# IGrevator.net
KiCad netlist of a schematic drawn in EAGLE
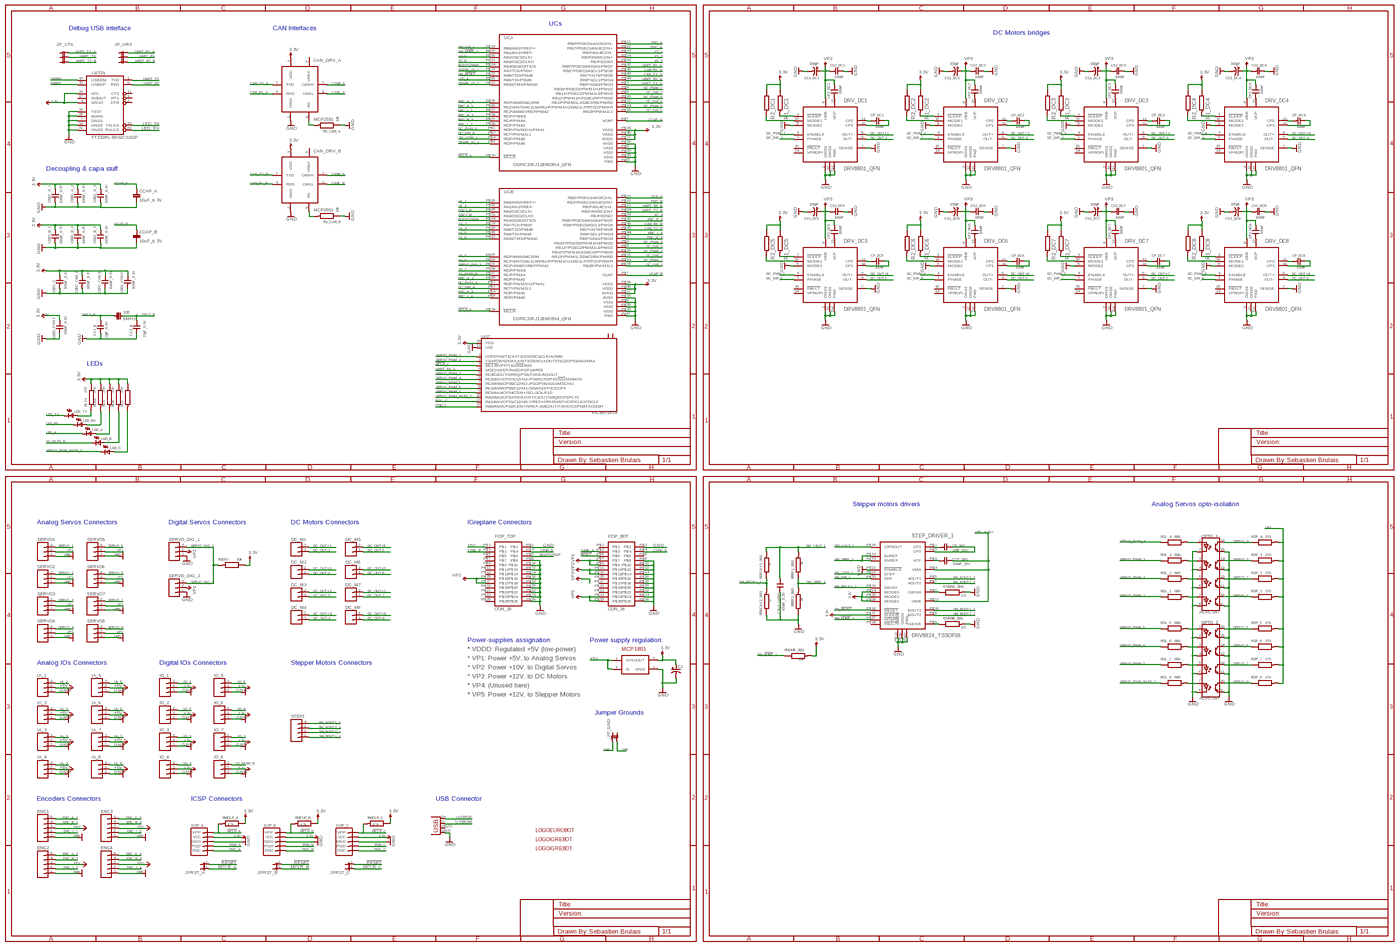
[diagram p0: schematic, sheet 1, overview]
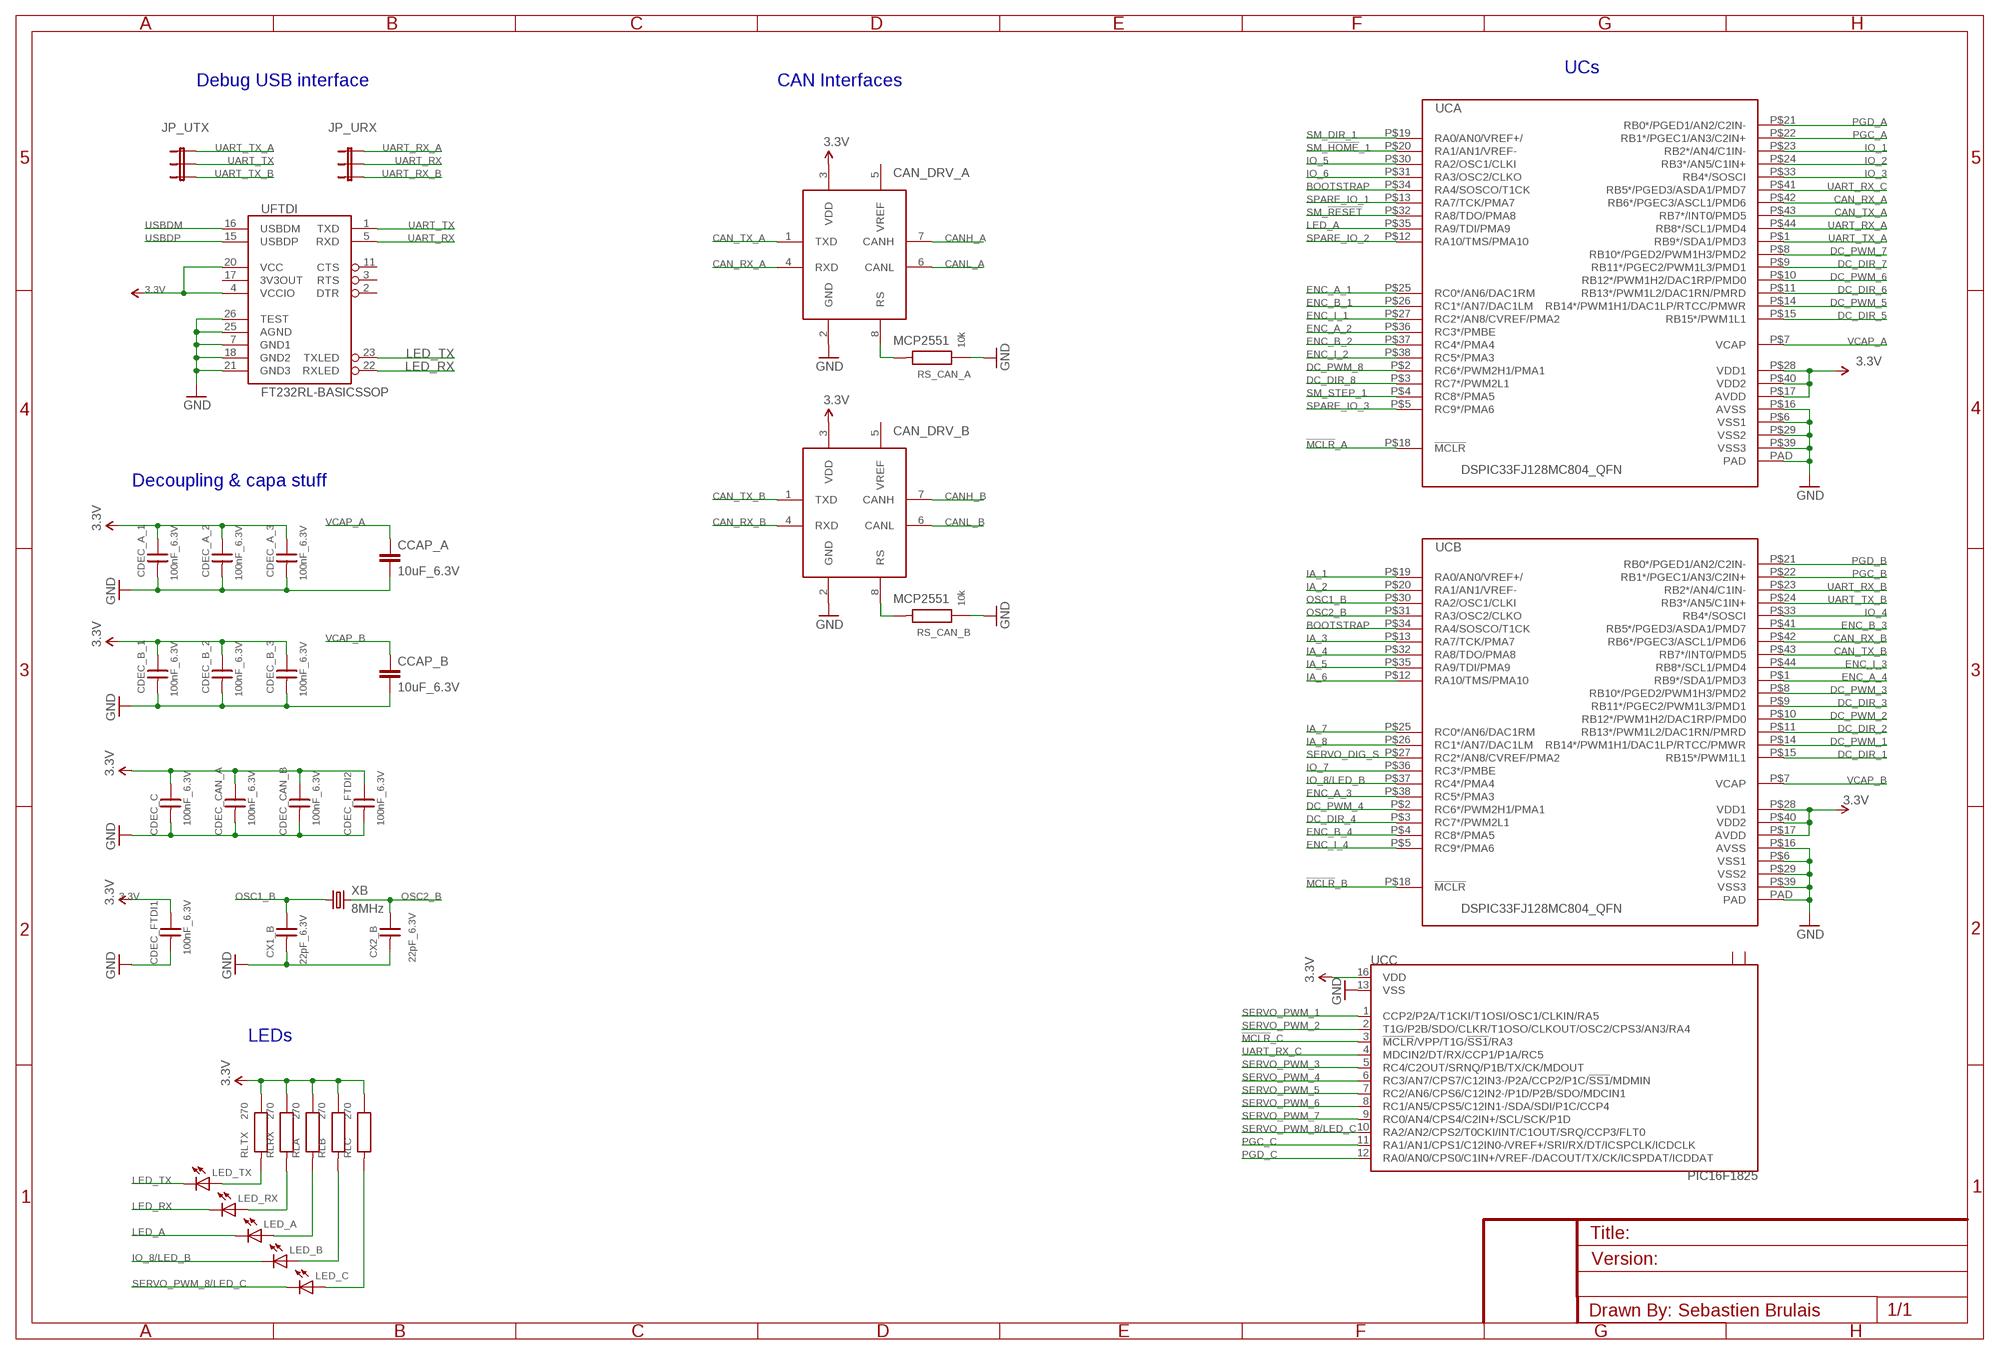
[diagram p1: schematic, sheet 1, part 1 of 4]
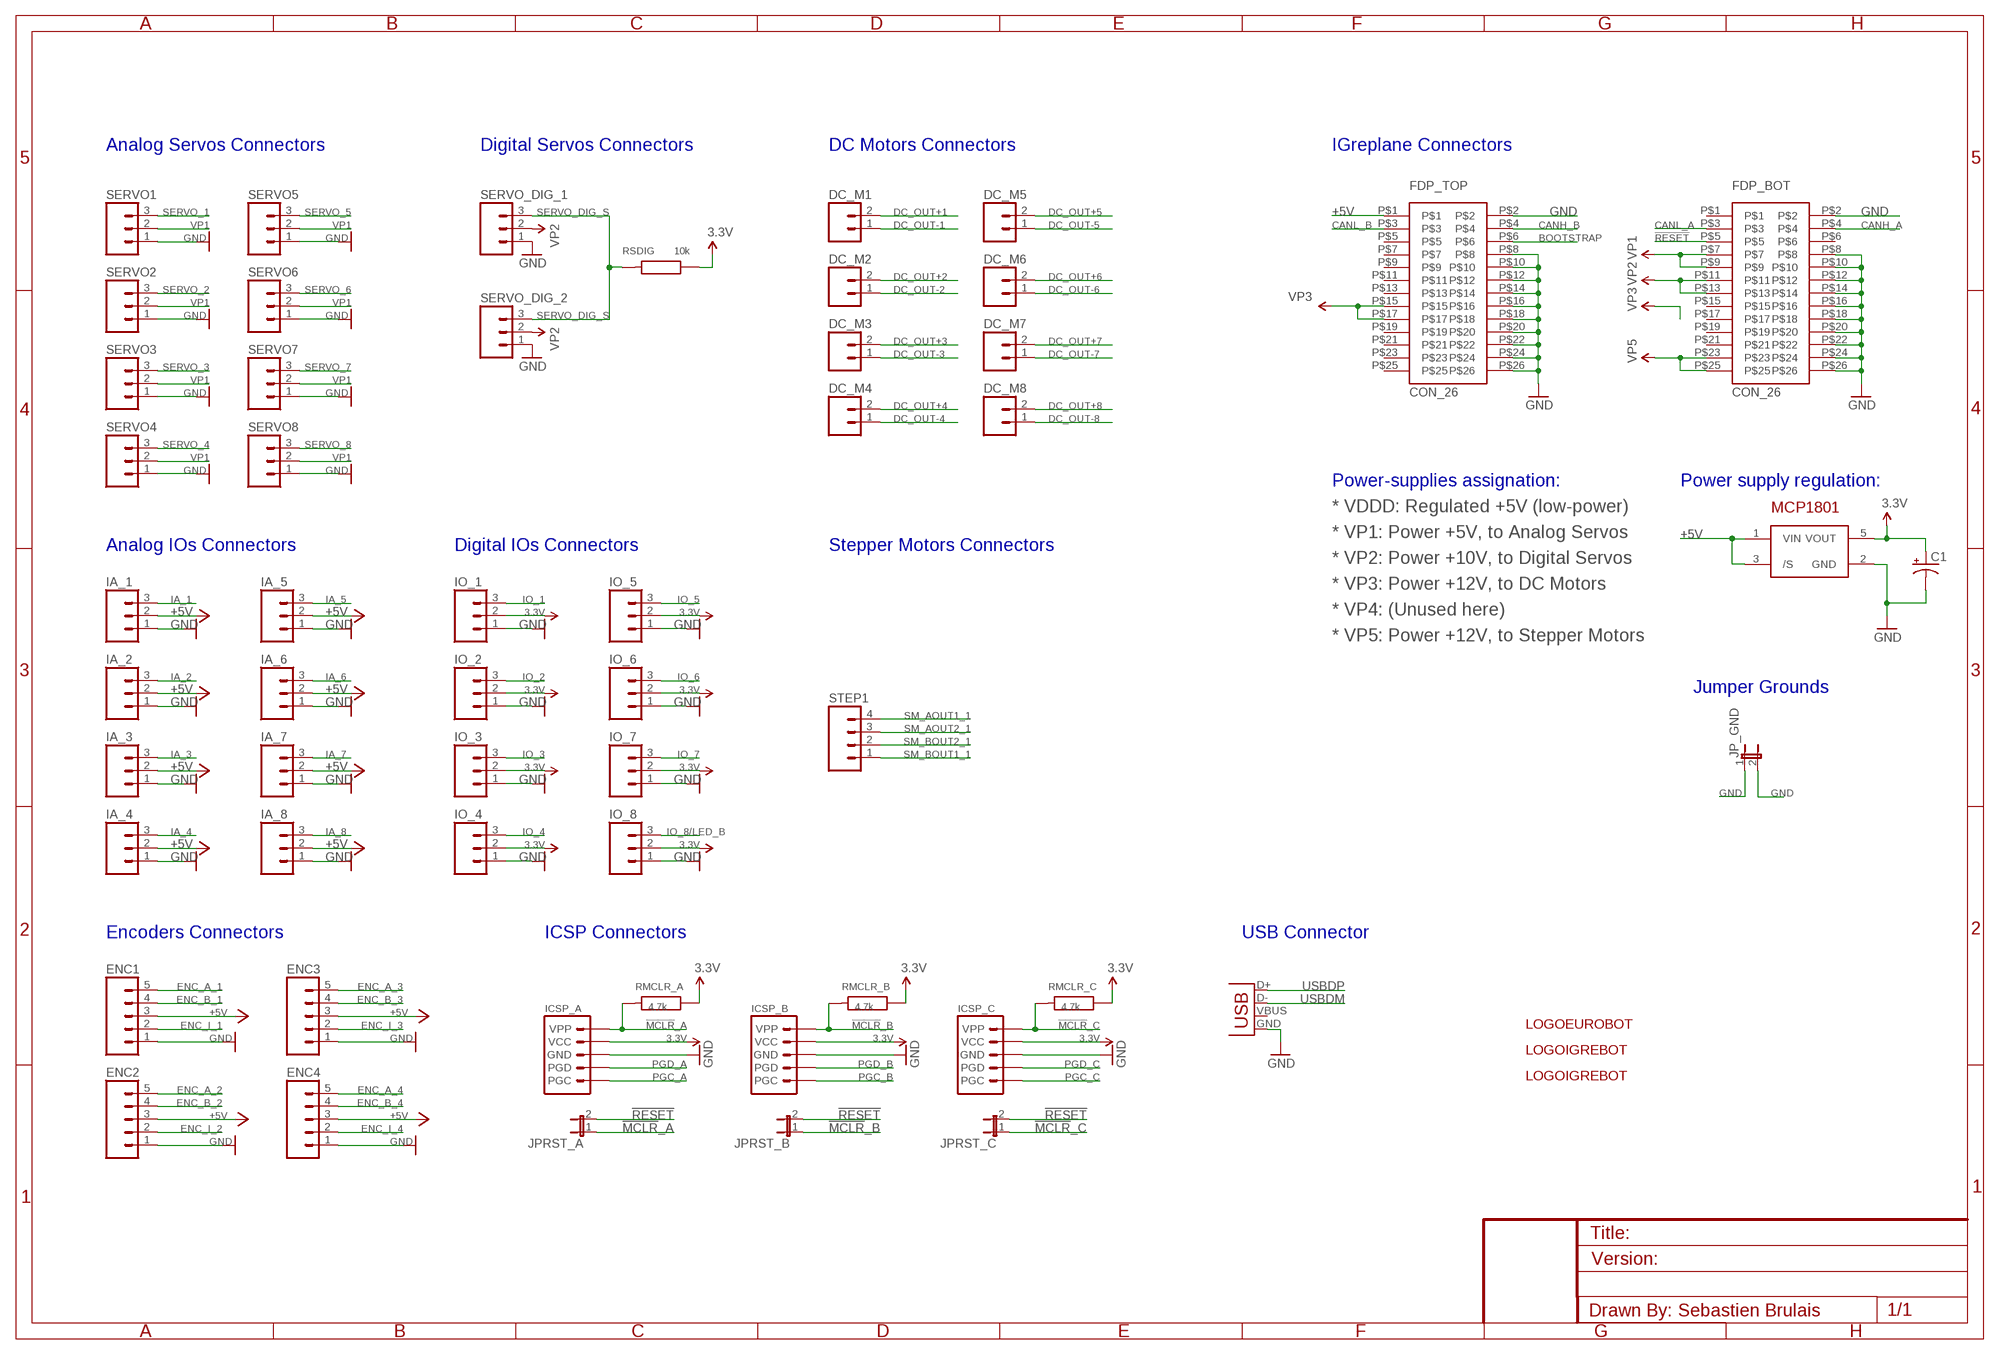
[diagram p2: schematic, sheet 1, part 2 of 4]
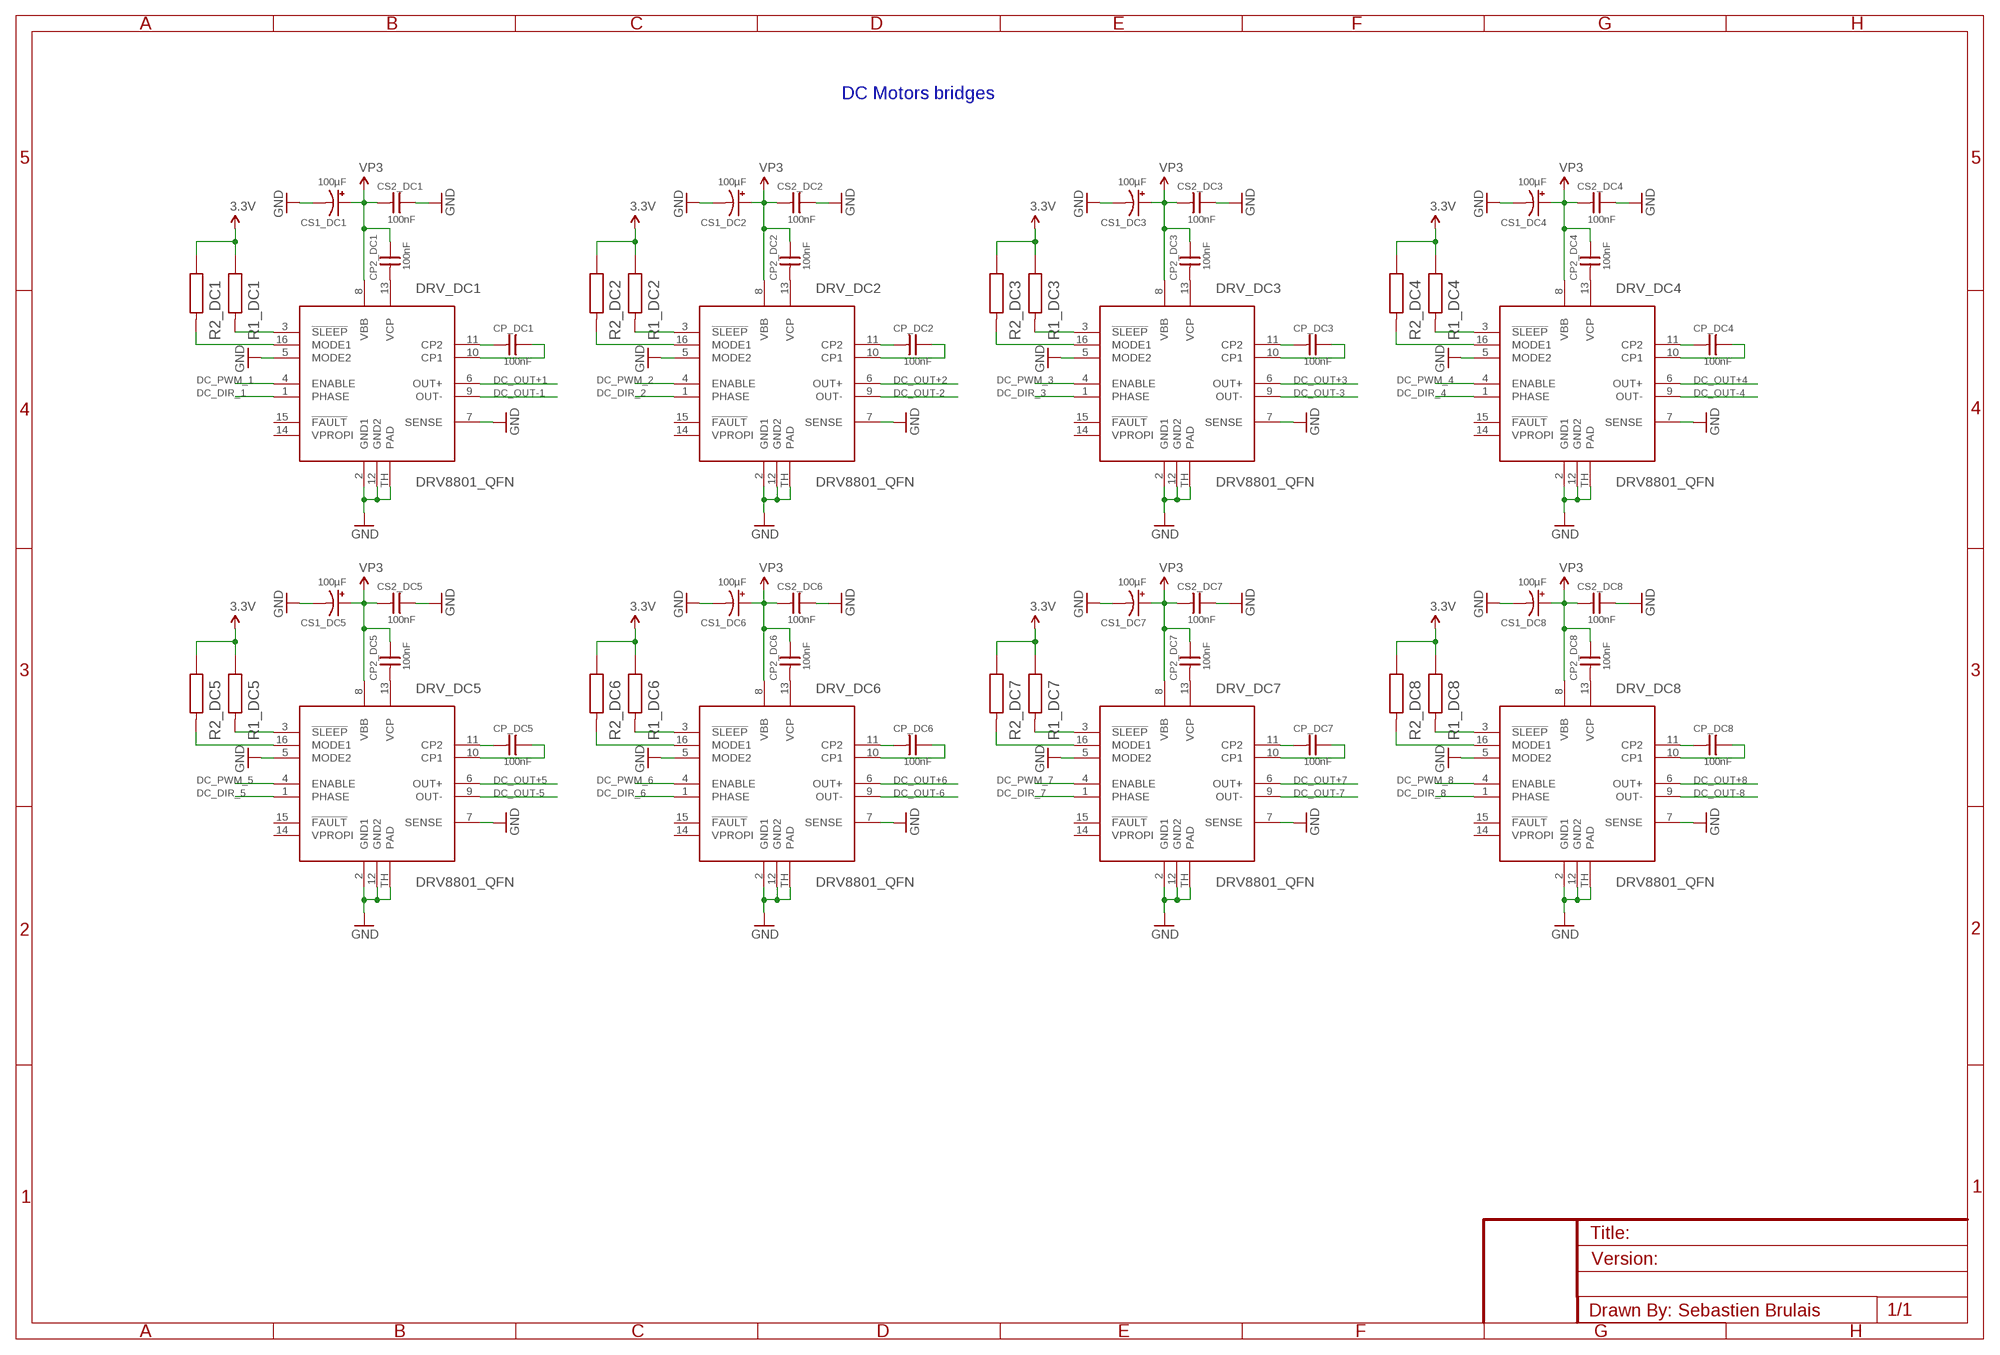
[diagram p3: schematic, sheet 1, part 3 of 4]
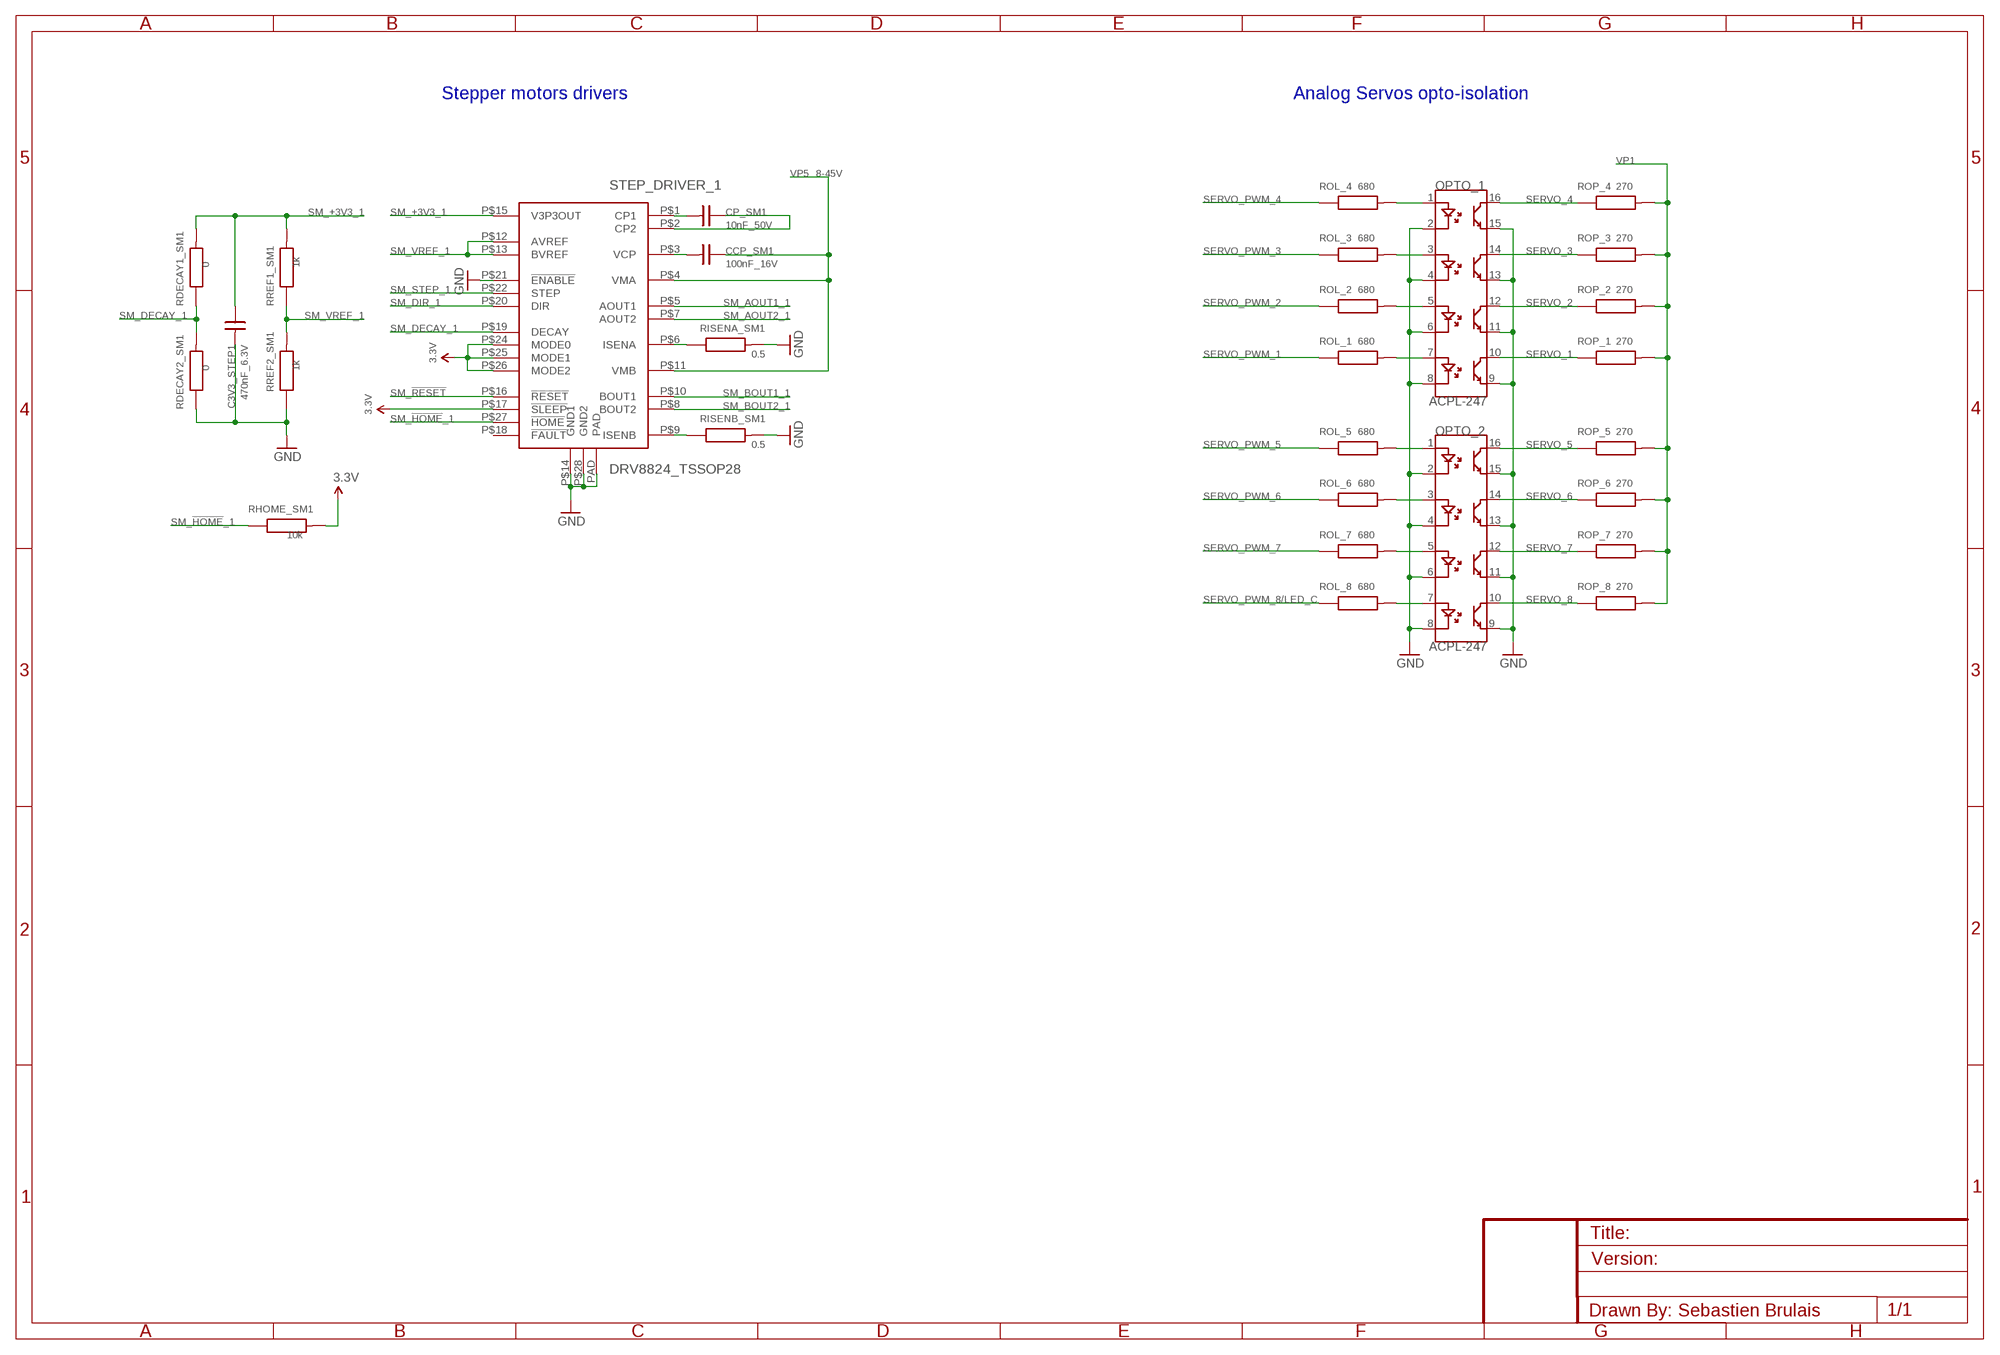
[diagram p4: schematic, sheet 1, part 4 of 4]

(export (version "E")
  (design (tool "Eeschema 10.0.6"))
  (components
    (comp (ref "C1")
      (value "CAP_POLC")
      (footprint "eagle-import:PANASONIC_C")
      (libsource (lib "eagle-import") (part "SparkFun-Passives_CAP_POLC"))
    )
    (comp (ref "C3V3_STEP1")
      (value "470nF_6.3V")
      (footprint "eagle-import:R0603")
      (libsource (lib "eagle-import") (part "C0603"))
    )
    (comp (ref "CAN_DRV_A")
      (value "MCP2551")
      (footprint "eagle-import:SO-08")
      (libsource (lib "eagle-import") (part "MCP2551"))
    )
    (comp (ref "CAN_DRV_B")
      (value "MCP2551")
      (footprint "eagle-import:SO-08")
      (libsource (lib "eagle-import") (part "MCP2551"))
    )
    (comp (ref "CCAP_A")
      (value "10uF_6.3V")
      (footprint "eagle-import:1206")
      (libsource (lib "eagle-import") (part "CAP1206"))
    )
    (comp (ref "CCAP_B")
      (value "10uF_6.3V")
      (footprint "eagle-import:1206")
      (libsource (lib "eagle-import") (part "CAP1206"))
    )
    (comp (ref "CCP_SM1")
      (value "100nF_16V")
      (footprint "eagle-import:R0603")
      (libsource (lib "eagle-import") (part "C0603"))
    )
    (comp (ref "CDEC_A_1")
      (value "100nF_6.3V")
      (footprint "eagle-import:R0603")
      (libsource (lib "eagle-import") (part "C0603"))
    )
    (comp (ref "CDEC_A_2")
      (value "100nF_6.3V")
      (footprint "eagle-import:R0603")
      (libsource (lib "eagle-import") (part "C0603"))
    )
    (comp (ref "CDEC_A_3")
      (value "100nF_6.3V")
      (footprint "eagle-import:R0603")
      (libsource (lib "eagle-import") (part "C0603"))
    )
    (comp (ref "CDEC_B_1")
      (value "100nF_6.3V")
      (footprint "eagle-import:R0603")
      (libsource (lib "eagle-import") (part "C0603"))
    )
    (comp (ref "CDEC_B_2")
      (value "100nF_6.3V")
      (footprint "eagle-import:R0603")
      (libsource (lib "eagle-import") (part "C0603"))
    )
    (comp (ref "CDEC_B_3")
      (value "100nF_6.3V")
      (footprint "eagle-import:R0603")
      (libsource (lib "eagle-import") (part "C0603"))
    )
    (comp (ref "CDEC_C")
      (value "100nF_6.3V")
      (footprint "eagle-import:R0603")
      (libsource (lib "eagle-import") (part "C0603"))
    )
    (comp (ref "CDEC_CAN_A")
      (value "100nF_6.3V")
      (footprint "eagle-import:R0603")
      (libsource (lib "eagle-import") (part "C0603"))
    )
    (comp (ref "CDEC_CAN_B")
      (value "100nF_6.3V")
      (footprint "eagle-import:R0603")
      (libsource (lib "eagle-import") (part "C0603"))
    )
    (comp (ref "CDEC_FTDI1")
      (value "100nF_6.3V")
      (footprint "eagle-import:R0603")
      (libsource (lib "eagle-import") (part "C0603"))
    )
    (comp (ref "CDEC_FTDI2")
      (value "100nF_6.3V")
      (footprint "eagle-import:R0603")
      (libsource (lib "eagle-import") (part "C0603"))
    )
    (comp (ref "CP2_DC1")
      (value "100nF")
      (footprint "eagle-import:R0603")
      (libsource (lib "eagle-import") (part "C0603"))
    )
    (comp (ref "CP2_DC2")
      (value "100nF")
      (footprint "eagle-import:R0603")
      (libsource (lib "eagle-import") (part "C0603"))
    )
    (comp (ref "CP2_DC3")
      (value "100nF")
      (footprint "eagle-import:R0603")
      (libsource (lib "eagle-import") (part "C0603"))
    )
    (comp (ref "CP2_DC4")
      (value "100nF")
      (footprint "eagle-import:R0603")
      (libsource (lib "eagle-import") (part "C0603"))
    )
    (comp (ref "CP2_DC5")
      (value "100nF")
      (footprint "eagle-import:R0603")
      (libsource (lib "eagle-import") (part "C0603"))
    )
    (comp (ref "CP2_DC6")
      (value "100nF")
      (footprint "eagle-import:R0603")
      (libsource (lib "eagle-import") (part "C0603"))
    )
    (comp (ref "CP2_DC7")
      (value "100nF")
      (footprint "eagle-import:R0603")
      (libsource (lib "eagle-import") (part "C0603"))
    )
    (comp (ref "CP2_DC8")
      (value "100nF")
      (footprint "eagle-import:R0603")
      (libsource (lib "eagle-import") (part "C0603"))
    )
    (comp (ref "CP_DC1")
      (value "100nF")
      (footprint "eagle-import:R0603")
      (libsource (lib "eagle-import") (part "C0603"))
    )
    (comp (ref "CP_DC2")
      (value "100nF")
      (footprint "eagle-import:R0603")
      (libsource (lib "eagle-import") (part "C0603"))
    )
    (comp (ref "CP_DC3")
      (value "100nF")
      (footprint "eagle-import:R0603")
      (libsource (lib "eagle-import") (part "C0603"))
    )
    (comp (ref "CP_DC4")
      (value "100nF")
      (footprint "eagle-import:R0603")
      (libsource (lib "eagle-import") (part "C0603"))
    )
    (comp (ref "CP_DC5")
      (value "100nF")
      (footprint "eagle-import:R0603")
      (libsource (lib "eagle-import") (part "C0603"))
    )
    (comp (ref "CP_DC6")
      (value "100nF")
      (footprint "eagle-import:R0603")
      (libsource (lib "eagle-import") (part "C0603"))
    )
    (comp (ref "CP_DC7")
      (value "100nF")
      (footprint "eagle-import:R0603")
      (libsource (lib "eagle-import") (part "C0603"))
    )
    (comp (ref "CP_DC8")
      (value "100nF")
      (footprint "eagle-import:R0603")
      (libsource (lib "eagle-import") (part "C0603"))
    )
    (comp (ref "CP_SM1")
      (value "10nF_50V")
      (footprint "eagle-import:R0603")
      (libsource (lib "eagle-import") (part "C0603"))
    )
    (comp (ref "CS1_DC1")
      (value "100µF")
      (footprint "eagle-import:PANASONIC_D")
      (libsource (lib "eagle-import") (part "CAP_POLD"))
    )
    (comp (ref "CS1_DC2")
      (value "100µF")
      (footprint "eagle-import:PANASONIC_D")
      (libsource (lib "eagle-import") (part "CAP_POLD"))
    )
    (comp (ref "CS1_DC3")
      (value "100µF")
      (footprint "eagle-import:PANASONIC_D")
      (libsource (lib "eagle-import") (part "CAP_POLD"))
    )
    (comp (ref "CS1_DC4")
      (value "100µF")
      (footprint "eagle-import:PANASONIC_D")
      (libsource (lib "eagle-import") (part "CAP_POLD"))
    )
    (comp (ref "CS1_DC5")
      (value "100µF")
      (footprint "eagle-import:PANASONIC_D")
      (libsource (lib "eagle-import") (part "CAP_POLD"))
    )
    (comp (ref "CS1_DC6")
      (value "100µF")
      (footprint "eagle-import:PANASONIC_D")
      (libsource (lib "eagle-import") (part "CAP_POLD"))
    )
    (comp (ref "CS1_DC7")
      (value "100µF")
      (footprint "eagle-import:PANASONIC_D")
      (libsource (lib "eagle-import") (part "CAP_POLD"))
    )
    (comp (ref "CS1_DC8")
      (value "100µF")
      (footprint "eagle-import:PANASONIC_D")
      (libsource (lib "eagle-import") (part "CAP_POLD"))
    )
    (comp (ref "CS2_DC1")
      (value "100nF")
      (footprint "eagle-import:R0603")
      (libsource (lib "eagle-import") (part "C0603"))
    )
    (comp (ref "CS2_DC2")
      (value "100nF")
      (footprint "eagle-import:R0603")
      (libsource (lib "eagle-import") (part "C0603"))
    )
    (comp (ref "CS2_DC3")
      (value "100nF")
      (footprint "eagle-import:R0603")
      (libsource (lib "eagle-import") (part "C0603"))
    )
    (comp (ref "CS2_DC4")
      (value "100nF")
      (footprint "eagle-import:R0603")
      (libsource (lib "eagle-import") (part "C0603"))
    )
    (comp (ref "CS2_DC5")
      (value "100nF")
      (footprint "eagle-import:R0603")
      (libsource (lib "eagle-import") (part "C0603"))
    )
    (comp (ref "CS2_DC6")
      (value "100nF")
      (footprint "eagle-import:R0603")
      (libsource (lib "eagle-import") (part "C0603"))
    )
    (comp (ref "CS2_DC7")
      (value "100nF")
      (footprint "eagle-import:R0603")
      (libsource (lib "eagle-import") (part "C0603"))
    )
    (comp (ref "CS2_DC8")
      (value "100nF")
      (footprint "eagle-import:R0603")
      (libsource (lib "eagle-import") (part "C0603"))
    )
    (comp (ref "CX1_B")
      (value "22pF_6.3V")
      (footprint "eagle-import:R0603")
      (libsource (lib "eagle-import") (part "C0603"))
    )
    (comp (ref "CX2_B")
      (value "22pF_6.3V")
      (footprint "eagle-import:R0603")
      (libsource (lib "eagle-import") (part "C0603"))
    )
    (comp (ref "DC_M1")
      (value "M02PTH")
      (footprint "eagle-import:1X02")
      (libsource (lib "eagle-import") (part "M02PTH"))
    )
    (comp (ref "DC_M2")
      (value "M02PTH")
      (footprint "eagle-import:1X02")
      (libsource (lib "eagle-import") (part "M02PTH"))
    )
    (comp (ref "DC_M3")
      (value "M02PTH")
      (footprint "eagle-import:1X02")
      (libsource (lib "eagle-import") (part "M02PTH"))
    )
    (comp (ref "DC_M4")
      (value "M02PTH")
      (footprint "eagle-import:1X02")
      (libsource (lib "eagle-import") (part "M02PTH"))
    )
    (comp (ref "DC_M5")
      (value "M02PTH")
      (footprint "eagle-import:1X02")
      (libsource (lib "eagle-import") (part "M02PTH"))
    )
    (comp (ref "DC_M6")
      (value "M02PTH")
      (footprint "eagle-import:1X02")
      (libsource (lib "eagle-import") (part "M02PTH"))
    )
    (comp (ref "DC_M7")
      (value "M02PTH")
      (footprint "eagle-import:1X02")
      (libsource (lib "eagle-import") (part "M02PTH"))
    )
    (comp (ref "DC_M8")
      (value "M02PTH")
      (footprint "eagle-import:1X02")
      (libsource (lib "eagle-import") (part "M02PTH"))
    )
    (comp (ref "DRV_DC1")
      (value "DRV8801_QFN")
      (footprint "eagle-import:QFN16")
      (libsource (lib "eagle-import") (part "DRV8801_QFN"))
    )
    (comp (ref "DRV_DC2")
      (value "DRV8801_QFN")
      (footprint "eagle-import:QFN16")
      (libsource (lib "eagle-import") (part "DRV8801_QFN"))
    )
    (comp (ref "DRV_DC3")
      (value "DRV8801_QFN")
      (footprint "eagle-import:QFN16")
      (libsource (lib "eagle-import") (part "DRV8801_QFN"))
    )
    (comp (ref "DRV_DC4")
      (value "DRV8801_QFN")
      (footprint "eagle-import:QFN16")
      (libsource (lib "eagle-import") (part "DRV8801_QFN"))
    )
    (comp (ref "DRV_DC5")
      (value "DRV8801_QFN")
      (footprint "eagle-import:QFN16")
      (libsource (lib "eagle-import") (part "DRV8801_QFN"))
    )
    (comp (ref "DRV_DC6")
      (value "DRV8801_QFN")
      (footprint "eagle-import:QFN16")
      (libsource (lib "eagle-import") (part "DRV8801_QFN"))
    )
    (comp (ref "DRV_DC7")
      (value "DRV8801_QFN")
      (footprint "eagle-import:QFN16")
      (libsource (lib "eagle-import") (part "DRV8801_QFN"))
    )
    (comp (ref "DRV_DC8")
      (value "DRV8801_QFN")
      (footprint "eagle-import:QFN16")
      (libsource (lib "eagle-import") (part "DRV8801_QFN"))
    )
    (comp (ref "ENC1")
      (value "M05PTH")
      (footprint "eagle-import:1X05")
      (libsource (lib "eagle-import") (part "M05PTH"))
    )
    (comp (ref "ENC2")
      (value "M05PTH")
      (footprint "eagle-import:1X05")
      (libsource (lib "eagle-import") (part "M05PTH"))
    )
    (comp (ref "ENC3")
      (value "M05PTH")
      (footprint "eagle-import:1X05")
      (libsource (lib "eagle-import") (part "M05PTH"))
    )
    (comp (ref "ENC4")
      (value "M05PTH")
      (footprint "eagle-import:1X05")
      (libsource (lib "eagle-import") (part "M05PTH"))
    )
    (comp (ref "FDP_BOT")
      (value "CON_26")
      (footprint "eagle-import:HE10-26_90")
      (libsource (lib "eagle-import") (part "CON_26"))
    )
    (comp (ref "FDP_TOP")
      (value "CON_26")
      (footprint "eagle-import:HE10-26_90")
      (libsource (lib "eagle-import") (part "CON_26"))
    )
    (comp (ref "IA_1")
      (value "M03PTH")
      (footprint "eagle-import:1X03")
      (libsource (lib "eagle-import") (part "M03PTH"))
    )
    (comp (ref "IA_2")
      (value "M03PTH")
      (footprint "eagle-import:1X03")
      (libsource (lib "eagle-import") (part "M03PTH"))
    )
    (comp (ref "IA_3")
      (value "M03PTH")
      (footprint "eagle-import:1X03")
      (libsource (lib "eagle-import") (part "M03PTH"))
    )
    (comp (ref "IA_4")
      (value "M03PTH")
      (footprint "eagle-import:1X03")
      (libsource (lib "eagle-import") (part "M03PTH"))
    )
    (comp (ref "IA_5")
      (value "M03PTH")
      (footprint "eagle-import:1X03")
      (libsource (lib "eagle-import") (part "M03PTH"))
    )
    (comp (ref "IA_6")
      (value "M03PTH")
      (footprint "eagle-import:1X03")
      (libsource (lib "eagle-import") (part "M03PTH"))
    )
    (comp (ref "IA_7")
      (value "M03PTH")
      (footprint "eagle-import:1X03")
      (libsource (lib "eagle-import") (part "M03PTH"))
    )
    (comp (ref "IA_8")
      (value "M03PTH")
      (footprint "eagle-import:1X03")
      (libsource (lib "eagle-import") (part "M03PTH"))
    )
    (comp (ref "ICSP_A")
      (value "PIC-ICSP-MINI")
      (footprint "eagle-import:PIC-ICSP-MINI")
      (libsource (lib "eagle-import") (part "PIC-ICSP-MINI"))
    )
    (comp (ref "ICSP_B")
      (value "PIC-ICSP-MINI")
      (footprint "eagle-import:PIC-ICSP-MINI")
      (libsource (lib "eagle-import") (part "PIC-ICSP-MINI"))
    )
    (comp (ref "ICSP_C")
      (value "PIC-ICSP-MINI")
      (footprint "eagle-import:PIC-ICSP-MINI")
      (libsource (lib "eagle-import") (part "PIC-ICSP-MINI"))
    )
    (comp (ref "IO_1")
      (value "M03PTH")
      (footprint "eagle-import:1X03")
      (libsource (lib "eagle-import") (part "M03PTH"))
    )
    (comp (ref "IO_2")
      (value "M03PTH")
      (footprint "eagle-import:1X03")
      (libsource (lib "eagle-import") (part "M03PTH"))
    )
    (comp (ref "IO_3")
      (value "M03PTH")
      (footprint "eagle-import:1X03")
      (libsource (lib "eagle-import") (part "M03PTH"))
    )
    (comp (ref "IO_4")
      (value "M03PTH")
      (footprint "eagle-import:1X03")
      (libsource (lib "eagle-import") (part "M03PTH"))
    )
    (comp (ref "IO_5")
      (value "M03PTH")
      (footprint "eagle-import:1X03")
      (libsource (lib "eagle-import") (part "M03PTH"))
    )
    (comp (ref "IO_6")
      (value "M03PTH")
      (footprint "eagle-import:1X03")
      (libsource (lib "eagle-import") (part "M03PTH"))
    )
    (comp (ref "IO_7")
      (value "M03PTH")
      (footprint "eagle-import:1X03")
      (libsource (lib "eagle-import") (part "M03PTH"))
    )
    (comp (ref "IO_8")
      (value "M03PTH")
      (footprint "eagle-import:1X03")
      (libsource (lib "eagle-import") (part "M03PTH"))
    )
    (comp (ref "JPRST_A")
      (value "JUMPER-2PTH_LOCK")
      (footprint "eagle-import:1X02_LOCK")
      (libsource (lib "eagle-import") (part "JUMPER-2PTH_LOCK"))
    )
    (comp (ref "JPRST_B")
      (value "JUMPER-2PTH_LOCK")
      (footprint "eagle-import:1X02_LOCK")
      (libsource (lib "eagle-import") (part "JUMPER-2PTH_LOCK"))
    )
    (comp (ref "JPRST_C")
      (value "JUMPER-2PTH_LOCK")
      (footprint "eagle-import:1X02_LOCK")
      (libsource (lib "eagle-import") (part "JUMPER-2PTH_LOCK"))
    )
    (comp (ref "JP_GND")
      (value "JUMPER-2PTH_LOCK")
      (footprint "eagle-import:1X02_LOCK")
      (libsource (lib "eagle-import") (part "SparkFun-Passives_JUMPER-2PTH_LOCK"))
    )
    (comp (ref "JP_URX")
      (value "JUMPER-3PTH")
      (footprint "eagle-import:1X03")
      (libsource (lib "eagle-import") (part "JUMPER-3PTH"))
    )
    (comp (ref "JP_UTX")
      (value "JUMPER-3PTH")
      (footprint "eagle-import:1X03")
      (libsource (lib "eagle-import") (part "JUMPER-3PTH"))
    )
    (comp (ref "LED_A")
      (value "LED0603")
      (footprint "eagle-import:LED-0603")
      (libsource (lib "eagle-import") (part "LED0603"))
    )
    (comp (ref "LED_B")
      (value "LED0603")
      (footprint "eagle-import:LED-0603")
      (libsource (lib "eagle-import") (part "LED0603"))
    )
    (comp (ref "LED_C")
      (value "LED0603")
      (footprint "eagle-import:LED-0603")
      (libsource (lib "eagle-import") (part "LED0603"))
    )
    (comp (ref "LED_RX")
      (value "LED0603")
      (footprint "eagle-import:LED-0603")
      (libsource (lib "eagle-import") (part "LED0603"))
    )
    (comp (ref "LED_TX")
      (value "LED0603")
      (footprint "eagle-import:LED-0603")
      (libsource (lib "eagle-import") (part "LED0603"))
    )
    (comp (ref "OPTO_1")
      (value "ACPL-247")
      (footprint "eagle-import:SOIC16")
      (libsource (lib "eagle-import") (part "ACPL-247"))
    )
    (comp (ref "OPTO_2")
      (value "ACPL-247")
      (footprint "eagle-import:SOIC16")
      (libsource (lib "eagle-import") (part "ACPL-247"))
    )
    (comp (ref "R1_DC1")
      (value "R0603")
      (footprint "eagle-import:R0603")
      (libsource (lib "eagle-import") (part "R0603"))
    )
    (comp (ref "R1_DC2")
      (value "R0603")
      (footprint "eagle-import:R0603")
      (libsource (lib "eagle-import") (part "R0603"))
    )
    (comp (ref "R1_DC3")
      (value "R0603")
      (footprint "eagle-import:R0603")
      (libsource (lib "eagle-import") (part "R0603"))
    )
    (comp (ref "R1_DC4")
      (value "R0603")
      (footprint "eagle-import:R0603")
      (libsource (lib "eagle-import") (part "R0603"))
    )
    (comp (ref "R1_DC5")
      (value "R0603")
      (footprint "eagle-import:R0603")
      (libsource (lib "eagle-import") (part "R0603"))
    )
    (comp (ref "R1_DC6")
      (value "R0603")
      (footprint "eagle-import:R0603")
      (libsource (lib "eagle-import") (part "R0603"))
    )
    (comp (ref "R1_DC7")
      (value "R0603")
      (footprint "eagle-import:R0603")
      (libsource (lib "eagle-import") (part "R0603"))
    )
    (comp (ref "R1_DC8")
      (value "R0603")
      (footprint "eagle-import:R0603")
      (libsource (lib "eagle-import") (part "R0603"))
    )
    (comp (ref "R2_DC1")
      (value "R0603")
      (footprint "eagle-import:R0603")
      (libsource (lib "eagle-import") (part "R0603"))
    )
    (comp (ref "R2_DC2")
      (value "R0603")
      (footprint "eagle-import:R0603")
      (libsource (lib "eagle-import") (part "R0603"))
    )
    (comp (ref "R2_DC3")
      (value "R0603")
      (footprint "eagle-import:R0603")
      (libsource (lib "eagle-import") (part "R0603"))
    )
    (comp (ref "R2_DC4")
      (value "R0603")
      (footprint "eagle-import:R0603")
      (libsource (lib "eagle-import") (part "R0603"))
    )
    (comp (ref "R2_DC5")
      (value "R0603")
      (footprint "eagle-import:R0603")
      (libsource (lib "eagle-import") (part "R0603"))
    )
    (comp (ref "R2_DC6")
      (value "R0603")
      (footprint "eagle-import:R0603")
      (libsource (lib "eagle-import") (part "R0603"))
    )
    (comp (ref "R2_DC7")
      (value "R0603")
      (footprint "eagle-import:R0603")
      (libsource (lib "eagle-import") (part "R0603"))
    )
    (comp (ref "R2_DC8")
      (value "R0603")
      (footprint "eagle-import:R0603")
      (libsource (lib "eagle-import") (part "R0603"))
    )
    (comp (ref "RDECAY1_SM1")
      (value "0")
      (footprint "eagle-import:R0603")
      (libsource (lib "eagle-import") (part "R0603"))
    )
    (comp (ref "RDECAY2_SM1")
      (value "0")
      (footprint "eagle-import:R0603")
      (libsource (lib "eagle-import") (part "R0603"))
    )
    (comp (ref "REG_3_3V")
      (value "MCP1801")
      (footprint "eagle-import:SOT23-5L")
      (libsource (lib "eagle-import") (part "MCP1801"))
    )
    (comp (ref "RHOME_SM1")
      (value "10k")
      (footprint "eagle-import:R0603")
      (libsource (lib "eagle-import") (part "R0603"))
    )
    (comp (ref "RISENA_SM1")
      (value "0.5")
      (footprint "eagle-import:R0603")
      (libsource (lib "eagle-import") (part "R0603"))
    )
    (comp (ref "RISENB_SM1")
      (value "0.5")
      (footprint "eagle-import:R0603")
      (libsource (lib "eagle-import") (part "R0603"))
    )
    (comp (ref "RLA")
      (value "270")
      (footprint "eagle-import:R0603")
      (libsource (lib "eagle-import") (part "R0603"))
    )
    (comp (ref "RLB")
      (value "270")
      (footprint "eagle-import:R0603")
      (libsource (lib "eagle-import") (part "R0603"))
    )
    (comp (ref "RLC")
      (value "270")
      (footprint "eagle-import:R0603")
      (libsource (lib "eagle-import") (part "R0603"))
    )
    (comp (ref "RLRX")
      (value "270")
      (footprint "eagle-import:R0603")
      (libsource (lib "eagle-import") (part "R0603"))
    )
    (comp (ref "RLTX")
      (value "270")
      (footprint "eagle-import:R0603")
      (libsource (lib "eagle-import") (part "R0603"))
    )
    (comp (ref "RMCLR_A")
      (value "4.7k")
      (footprint "eagle-import:R0603")
      (libsource (lib "eagle-import") (part "R0603"))
    )
    (comp (ref "RMCLR_B")
      (value "4.7k")
      (footprint "eagle-import:R0603")
      (libsource (lib "eagle-import") (part "R0603"))
    )
    (comp (ref "RMCLR_C")
      (value "4.7k")
      (footprint "eagle-import:R0603")
      (libsource (lib "eagle-import") (part "R0603"))
    )
    (comp (ref "ROL_1")
      (value "680")
      (footprint "eagle-import:R0603")
      (libsource (lib "eagle-import") (part "R0603"))
    )
    (comp (ref "ROL_2")
      (value "680")
      (footprint "eagle-import:R0603")
      (libsource (lib "eagle-import") (part "R0603"))
    )
    (comp (ref "ROL_3")
      (value "680")
      (footprint "eagle-import:R0603")
      (libsource (lib "eagle-import") (part "R0603"))
    )
    (comp (ref "ROL_4")
      (value "680")
      (footprint "eagle-import:R0603")
      (libsource (lib "eagle-import") (part "R0603"))
    )
    (comp (ref "ROL_5")
      (value "680")
      (footprint "eagle-import:R0603")
      (libsource (lib "eagle-import") (part "R0603"))
    )
    (comp (ref "ROL_6")
      (value "680")
      (footprint "eagle-import:R0603")
      (libsource (lib "eagle-import") (part "R0603"))
    )
    (comp (ref "ROL_7")
      (value "680")
      (footprint "eagle-import:R0603")
      (libsource (lib "eagle-import") (part "R0603"))
    )
    (comp (ref "ROL_8")
      (value "680")
      (footprint "eagle-import:R0603")
      (libsource (lib "eagle-import") (part "R0603"))
    )
    (comp (ref "ROP_1")
      (value "270")
      (footprint "eagle-import:R0603")
      (libsource (lib "eagle-import") (part "R0603"))
    )
    (comp (ref "ROP_2")
      (value "270")
      (footprint "eagle-import:R0603")
      (libsource (lib "eagle-import") (part "R0603"))
    )
    (comp (ref "ROP_3")
      (value "270")
      (footprint "eagle-import:R0603")
      (libsource (lib "eagle-import") (part "R0603"))
    )
    (comp (ref "ROP_4")
      (value "270")
      (footprint "eagle-import:R0603")
      (libsource (lib "eagle-import") (part "R0603"))
    )
    (comp (ref "ROP_5")
      (value "270")
      (footprint "eagle-import:R0603")
      (libsource (lib "eagle-import") (part "R0603"))
    )
    (comp (ref "ROP_6")
      (value "270")
      (footprint "eagle-import:R0603")
      (libsource (lib "eagle-import") (part "R0603"))
    )
    (comp (ref "ROP_7")
      (value "270")
      (footprint "eagle-import:R0603")
      (libsource (lib "eagle-import") (part "R0603"))
    )
    (comp (ref "ROP_8")
      (value "270")
      (footprint "eagle-import:R0603")
      (libsource (lib "eagle-import") (part "R0603"))
    )
    (comp (ref "RREF1_SM1")
      (value "1k")
      (footprint "eagle-import:R0603")
      (libsource (lib "eagle-import") (part "R0603"))
    )
    (comp (ref "RREF2_SM1")
      (value "1k")
      (footprint "eagle-import:R0603")
      (libsource (lib "eagle-import") (part "R0603"))
    )
    (comp (ref "RSDIG")
      (value "10k")
      (footprint "eagle-import:R0603")
      (libsource (lib "eagle-import") (part "R0603"))
    )
    (comp (ref "RS_CAN_A")
      (value "10k")
      (footprint "eagle-import:R0603")
      (libsource (lib "eagle-import") (part "R0603"))
    )
    (comp (ref "RS_CAN_B")
      (value "10k")
      (footprint "eagle-import:R0603")
      (libsource (lib "eagle-import") (part "R0603"))
    )
    (comp (ref "SERVO1")
      (value "M03PTH")
      (footprint "eagle-import:1X03")
      (libsource (lib "eagle-import") (part "M03PTH"))
    )
    (comp (ref "SERVO2")
      (value "M03PTH")
      (footprint "eagle-import:1X03")
      (libsource (lib "eagle-import") (part "M03PTH"))
    )
    (comp (ref "SERVO3")
      (value "M03PTH")
      (footprint "eagle-import:1X03")
      (libsource (lib "eagle-import") (part "M03PTH"))
    )
    (comp (ref "SERVO4")
      (value "M03PTH")
      (footprint "eagle-import:1X03")
      (libsource (lib "eagle-import") (part "M03PTH"))
    )
    (comp (ref "SERVO5")
      (value "M03PTH")
      (footprint "eagle-import:1X03")
      (libsource (lib "eagle-import") (part "M03PTH"))
    )
    (comp (ref "SERVO6")
      (value "M03PTH")
      (footprint "eagle-import:1X03")
      (libsource (lib "eagle-import") (part "M03PTH"))
    )
    (comp (ref "SERVO7")
      (value "M03PTH")
      (footprint "eagle-import:1X03")
      (libsource (lib "eagle-import") (part "M03PTH"))
    )
    (comp (ref "SERVO8")
      (value "M03PTH")
      (footprint "eagle-import:1X03")
      (libsource (lib "eagle-import") (part "M03PTH"))
    )
    (comp (ref "SERVO_DIG_1")
      (value "M03PTH")
      (footprint "eagle-import:1X03")
      (libsource (lib "eagle-import") (part "M03PTH"))
    )
    (comp (ref "SERVO_DIG_2")
      (value "M03PTH")
      (footprint "eagle-import:1X03")
      (libsource (lib "eagle-import") (part "M03PTH"))
    )
    (comp (ref "STEP1")
      (value "M04PTH")
      (footprint "eagle-import:1X04")
      (libsource (lib "eagle-import") (part "M04PTH"))
    )
    (comp (ref "STEP_DRIVER_1")
      (value "DRV8824_TSSOP28")
      (footprint "eagle-import:TSSOP-28-PAD")
      (libsource (lib "eagle-import") (part "DRV8824_TSSOP28"))
    )
    (comp (ref "U$3")
      (value "LOGOEUROBOT")
      (footprint "eagle-import:LOGO_EUROBOT_1")
      (libsource (lib "eagle-import") (part "LOGOEUROBOT"))
    )
    (comp (ref "U$5")
      (value "LOGOIGREBOT")
      (footprint "eagle-import:LOGO_IGREBOT")
      (libsource (lib "eagle-import") (part "LOGOIGREBOT"))
    )
    (comp (ref "U$10")
      (value "LOGOIGREBOT")
      (footprint "eagle-import:LOGO_IGREBOT")
      (libsource (lib "eagle-import") (part "LOGOIGREBOT"))
    )
    (comp (ref "UCA")
      (value "DSPIC33FJ128MC804_QFN")
      (footprint "eagle-import:QFN44-8X8")
      (libsource (lib "eagle-import") (part "DSPIC33FJ128MC804_QFN"))
    )
    (comp (ref "UCB")
      (value "DSPIC33FJ128MC804_QFN")
      (footprint "eagle-import:QFN44-8X8")
      (libsource (lib "eagle-import") (part "DSPIC33FJ128MC804_QFN"))
    )
    (comp (ref "UCC")
      (value "PIC16F1825")
      (footprint "eagle-import:QFN16-0.65")
      (libsource (lib "eagle-import") (part "PIC16F1825"))
    )
    (comp (ref "UFTDI")
      (value "FT232RL-BASICSSOP")
      (footprint "eagle-import:SSOP28DB")
      (libsource (lib "eagle-import") (part "FT232RL-BASICSSOP"))
    )
    (comp (ref "X1")
      (value "USBSMD")
      (footprint "eagle-import:USB-MINIB")
      (libsource (lib "eagle-import") (part "USBSMD"))
    )
    (comp (ref "XB")
      (value "8MHz")
      (footprint "eagle-import:XTAL_4.9-1.8")
      (libsource (lib "eagle-import") (part "XTAL4.8_1.8"))
    )
  )
  (nets
    (net (code "1") (name "+5V") (class "Default")
      (node (ref "ENC1") (pin "3") (pinfunction "3_3") (pintype "passive"))
      (node (ref "ENC2") (pin "3") (pinfunction "3_3") (pintype "passive"))
      (node (ref "ENC3") (pin "3") (pinfunction "3_3") (pintype "passive"))
      (node (ref "ENC4") (pin "3") (pinfunction "3_3") (pintype "passive"))
      (node (ref "FDP_TOP") (pin "P$1") (pinfunction "P$1_P$1") (pintype "bidirectional"))
      (node (ref "IA_1") (pin "2") (pinfunction "2_2") (pintype "passive"))
      (node (ref "IA_2") (pin "2") (pinfunction "2_2") (pintype "passive"))
      (node (ref "IA_3") (pin "2") (pinfunction "2_2") (pintype "passive"))
      (node (ref "IA_4") (pin "2") (pinfunction "2_2") (pintype "passive"))
      (node (ref "IA_5") (pin "2") (pinfunction "2_2") (pintype "passive"))
      (node (ref "IA_6") (pin "2") (pinfunction "2_2") (pintype "passive"))
      (node (ref "IA_7") (pin "2") (pinfunction "2_2") (pintype "passive"))
      (node (ref "IA_8") (pin "2") (pinfunction "2_2") (pintype "passive"))
      (node (ref "REG_3_3V") (pin "1") (pinfunction "VIN_1") (pintype "bidirectional"))
      (node (ref "REG_3_3V") (pin "3") (pinfunction "/S_3") (pintype "bidirectional"))
    )
    (net (code "2") (name "/BOOTSTRAP") (class "Default")
      (node (ref "FDP_TOP") (pin "P$6") (pinfunction "P$6_P$6") (pintype "bidirectional"))
      (node (ref "UCA") (pin "P$34") (pinfunction "RA4/SOSCO/T1CK_P$34") (pintype "bidirectional"))
      (node (ref "UCB") (pin "P$34") (pinfunction "RA4/SOSCO/T1CK_P$34") (pintype "bidirectional"))
    )
    (net (code "3") (name "/CANH_A") (class "Default")
      (node (ref "CAN_DRV_A") (pin "7") (pinfunction "CANH_7") (pintype "bidirectional"))
      (node (ref "FDP_BOT") (pin "P$4") (pinfunction "P$4_P$4") (pintype "bidirectional"))
    )
    (net (code "4") (name "/CANH_B") (class "Default")
      (node (ref "CAN_DRV_B") (pin "7") (pinfunction "CANH_7") (pintype "bidirectional"))
      (node (ref "FDP_TOP") (pin "P$4") (pinfunction "P$4_P$4") (pintype "bidirectional"))
    )
    (net (code "5") (name "/CANL_A") (class "Default")
      (node (ref "CAN_DRV_A") (pin "6") (pinfunction "CANL_6") (pintype "bidirectional"))
      (node (ref "FDP_BOT") (pin "P$3") (pinfunction "P$3_P$3") (pintype "bidirectional"))
    )
    (net (code "6") (name "/CANL_B") (class "Default")
      (node (ref "CAN_DRV_B") (pin "6") (pinfunction "CANL_6") (pintype "bidirectional"))
      (node (ref "FDP_TOP") (pin "P$3") (pinfunction "P$3_P$3") (pintype "bidirectional"))
    )
    (net (code "7") (name "/CAN_RX_A") (class "Default")
      (node (ref "CAN_DRV_A") (pin "4") (pinfunction "RXD_4") (pintype "bidirectional"))
      (node (ref "UCA") (pin "P$42") (pinfunction "RB6*/PGEC3/ASCL1/PMD6_P$42") (pintype "bidirectional"))
    )
    (net (code "8") (name "/CAN_RX_B") (class "Default")
      (node (ref "CAN_DRV_B") (pin "4") (pinfunction "RXD_4") (pintype "bidirectional"))
      (node (ref "UCB") (pin "P$42") (pinfunction "RB6*/PGEC3/ASCL1/PMD6_P$42") (pintype "bidirectional"))
    )
    (net (code "9") (name "/CAN_TX_A") (class "Default")
      (node (ref "CAN_DRV_A") (pin "1") (pinfunction "TXD_1") (pintype "bidirectional"))
      (node (ref "UCA") (pin "P$43") (pinfunction "RB7*/INT0/PMD5_P$43") (pintype "bidirectional"))
    )
    (net (code "10") (name "/CAN_TX_B") (class "Default")
      (node (ref "CAN_DRV_B") (pin "1") (pinfunction "TXD_1") (pintype "bidirectional"))
      (node (ref "UCB") (pin "P$43") (pinfunction "RB7*/INT0/PMD5_P$43") (pintype "bidirectional"))
    )
    (net (code "11") (name "/DC_DIR_1") (class "Default")
      (node (ref "DRV_DC1") (pin "1") (pinfunction "PHASE_1") (pintype "bidirectional"))
      (node (ref "UCB") (pin "P$15") (pinfunction "RB15*/PWM1L1_P$15") (pintype "bidirectional"))
    )
    (net (code "12") (name "/DC_DIR_2") (class "Default")
      (node (ref "DRV_DC2") (pin "1") (pinfunction "PHASE_1") (pintype "bidirectional"))
      (node (ref "UCB") (pin "P$11") (pinfunction "RB13*/PWM1L2/DAC1RN/PMRD_P$11") (pintype "bidirectional"))
    )
    (net (code "13") (name "/DC_DIR_3") (class "Default")
      (node (ref "DRV_DC3") (pin "1") (pinfunction "PHASE_1") (pintype "bidirectional"))
      (node (ref "UCB") (pin "P$9") (pinfunction "RB11*/PGEC2/PWM1L3/PMD1_P$9") (pintype "bidirectional"))
    )
    (net (code "14") (name "/DC_DIR_4") (class "Default")
      (node (ref "DRV_DC4") (pin "1") (pinfunction "PHASE_1") (pintype "bidirectional"))
      (node (ref "UCB") (pin "P$3") (pinfunction "RC7*/PWM2L1_P$3") (pintype "bidirectional"))
    )
    (net (code "15") (name "/DC_DIR_5") (class "Default")
      (node (ref "DRV_DC5") (pin "1") (pinfunction "PHASE_1") (pintype "bidirectional"))
      (node (ref "UCA") (pin "P$15") (pinfunction "RB15*/PWM1L1_P$15") (pintype "bidirectional"))
    )
    (net (code "16") (name "/DC_DIR_6") (class "Default")
      (node (ref "DRV_DC6") (pin "1") (pinfunction "PHASE_1") (pintype "bidirectional"))
      (node (ref "UCA") (pin "P$11") (pinfunction "RB13*/PWM1L2/DAC1RN/PMRD_P$11") (pintype "bidirectional"))
    )
    (net (code "17") (name "/DC_DIR_7") (class "Default")
      (node (ref "DRV_DC7") (pin "1") (pinfunction "PHASE_1") (pintype "bidirectional"))
      (node (ref "UCA") (pin "P$9") (pinfunction "RB11*/PGEC2/PWM1L3/PMD1_P$9") (pintype "bidirectional"))
    )
    (net (code "18") (name "/DC_DIR_8") (class "Default")
      (node (ref "DRV_DC8") (pin "1") (pinfunction "PHASE_1") (pintype "bidirectional"))
      (node (ref "UCA") (pin "P$3") (pinfunction "RC7*/PWM2L1_P$3") (pintype "bidirectional"))
    )
    (net (code "19") (name "/DC_OUT+1") (class "Default")
      (node (ref "DC_M1") (pin "2") (pinfunction "2_2") (pintype "passive"))
      (node (ref "DRV_DC1") (pin "6") (pinfunction "OUT+_6") (pintype "bidirectional"))
    )
    (net (code "20") (name "/DC_OUT+2") (class "Default")
      (node (ref "DC_M2") (pin "2") (pinfunction "2_2") (pintype "passive"))
      (node (ref "DRV_DC2") (pin "6") (pinfunction "OUT+_6") (pintype "bidirectional"))
    )
    (net (code "21") (name "/DC_OUT+3") (class "Default")
      (node (ref "DC_M3") (pin "2") (pinfunction "2_2") (pintype "passive"))
      (node (ref "DRV_DC3") (pin "6") (pinfunction "OUT+_6") (pintype "bidirectional"))
    )
    (net (code "22") (name "/DC_OUT+4") (class "Default")
      (node (ref "DC_M4") (pin "2") (pinfunction "2_2") (pintype "passive"))
      (node (ref "DRV_DC4") (pin "6") (pinfunction "OUT+_6") (pintype "bidirectional"))
    )
    (net (code "23") (name "/DC_OUT+5") (class "Default")
      (node (ref "DC_M5") (pin "2") (pinfunction "2_2") (pintype "passive"))
      (node (ref "DRV_DC5") (pin "6") (pinfunction "OUT+_6") (pintype "bidirectional"))
    )
    (net (code "24") (name "/DC_OUT+6") (class "Default")
      (node (ref "DC_M6") (pin "2") (pinfunction "2_2") (pintype "passive"))
      (node (ref "DRV_DC6") (pin "6") (pinfunction "OUT+_6") (pintype "bidirectional"))
    )
    (net (code "25") (name "/DC_OUT+7") (class "Default")
      (node (ref "DC_M7") (pin "2") (pinfunction "2_2") (pintype "passive"))
      (node (ref "DRV_DC7") (pin "6") (pinfunction "OUT+_6") (pintype "bidirectional"))
    )
    (net (code "26") (name "/DC_OUT+8") (class "Default")
      (node (ref "DC_M8") (pin "2") (pinfunction "2_2") (pintype "passive"))
      (node (ref "DRV_DC8") (pin "6") (pinfunction "OUT+_6") (pintype "bidirectional"))
    )
    (net (code "27") (name "/DC_OUT-1") (class "Default")
      (node (ref "DC_M1") (pin "1") (pinfunction "1_1") (pintype "passive"))
      (node (ref "DRV_DC1") (pin "9") (pinfunction "OUT-_9") (pintype "bidirectional"))
    )
    (net (code "28") (name "/DC_OUT-2") (class "Default")
      (node (ref "DC_M2") (pin "1") (pinfunction "1_1") (pintype "passive"))
      (node (ref "DRV_DC2") (pin "9") (pinfunction "OUT-_9") (pintype "bidirectional"))
    )
    (net (code "29") (name "/DC_OUT-3") (class "Default")
      (node (ref "DC_M3") (pin "1") (pinfunction "1_1") (pintype "passive"))
      (node (ref "DRV_DC3") (pin "9") (pinfunction "OUT-_9") (pintype "bidirectional"))
    )
    (net (code "30") (name "/DC_OUT-4") (class "Default")
      (node (ref "DC_M4") (pin "1") (pinfunction "1_1") (pintype "passive"))
      (node (ref "DRV_DC4") (pin "9") (pinfunction "OUT-_9") (pintype "bidirectional"))
    )
    (net (code "31") (name "/DC_OUT-5") (class "Default")
      (node (ref "DC_M5") (pin "1") (pinfunction "1_1") (pintype "passive"))
      (node (ref "DRV_DC5") (pin "9") (pinfunction "OUT-_9") (pintype "bidirectional"))
    )
    (net (code "32") (name "/DC_OUT-6") (class "Default")
      (node (ref "DC_M6") (pin "1") (pinfunction "1_1") (pintype "passive"))
      (node (ref "DRV_DC6") (pin "9") (pinfunction "OUT-_9") (pintype "bidirectional"))
    )
    (net (code "33") (name "/DC_OUT-7") (class "Default")
      (node (ref "DC_M7") (pin "1") (pinfunction "1_1") (pintype "passive"))
      (node (ref "DRV_DC7") (pin "9") (pinfunction "OUT-_9") (pintype "bidirectional"))
    )
    (net (code "34") (name "/DC_OUT-8") (class "Default")
      (node (ref "DC_M8") (pin "1") (pinfunction "1_1") (pintype "passive"))
      (node (ref "DRV_DC8") (pin "9") (pinfunction "OUT-_9") (pintype "bidirectional"))
    )
    (net (code "35") (name "/DC_PWM_1") (class "Default")
      (node (ref "DRV_DC1") (pin "4") (pinfunction "ENABLE_4") (pintype "bidirectional"))
      (node (ref "UCB") (pin "P$14") (pinfunction "RB14*/PWM1H1/DAC1LP/RTCC/PMWR_P$14") (pintype "bidirectional"))
    )
    (net (code "36") (name "/DC_PWM_2") (class "Default")
      (node (ref "DRV_DC2") (pin "4") (pinfunction "ENABLE_4") (pintype "bidirectional"))
      (node (ref "UCB") (pin "P$10") (pinfunction "RB12*/PWM1H2/DAC1RP/PMD0_P$10") (pintype "bidirectional"))
    )
    (net (code "37") (name "/DC_PWM_3") (class "Default")
      (node (ref "DRV_DC3") (pin "4") (pinfunction "ENABLE_4") (pintype "bidirectional"))
      (node (ref "UCB") (pin "P$8") (pinfunction "RB10*/PGED2/PWM1H3/PMD2_P$8") (pintype "bidirectional"))
    )
    (net (code "38") (name "/DC_PWM_4") (class "Default")
      (node (ref "DRV_DC4") (pin "4") (pinfunction "ENABLE_4") (pintype "bidirectional"))
      (node (ref "UCB") (pin "P$2") (pinfunction "RC6*/PWM2H1/PMA1_P$2") (pintype "bidirectional"))
    )
    (net (code "39") (name "/DC_PWM_5") (class "Default")
      (node (ref "DRV_DC5") (pin "4") (pinfunction "ENABLE_4") (pintype "bidirectional"))
      (node (ref "UCA") (pin "P$14") (pinfunction "RB14*/PWM1H1/DAC1LP/RTCC/PMWR_P$14") (pintype "bidirectional"))
    )
    (net (code "40") (name "/DC_PWM_6") (class "Default")
      (node (ref "DRV_DC6") (pin "4") (pinfunction "ENABLE_4") (pintype "bidirectional"))
      (node (ref "UCA") (pin "P$10") (pinfunction "RB12*/PWM1H2/DAC1RP/PMD0_P$10") (pintype "bidirectional"))
    )
    (net (code "41") (name "/DC_PWM_7") (class "Default")
      (node (ref "DRV_DC7") (pin "4") (pinfunction "ENABLE_4") (pintype "bidirectional"))
      (node (ref "UCA") (pin "P$8") (pinfunction "RB10*/PGED2/PWM1H3/PMD2_P$8") (pintype "bidirectional"))
    )
    (net (code "42") (name "/DC_PWM_8") (class "Default")
      (node (ref "DRV_DC8") (pin "4") (pinfunction "ENABLE_4") (pintype "bidirectional"))
      (node (ref "UCA") (pin "P$2") (pinfunction "RC6*/PWM2H1/PMA1_P$2") (pintype "bidirectional"))
    )
    (net (code "43") (name "/ENC_A_1") (class "Default")
      (node (ref "ENC1") (pin "5") (pinfunction "5_5") (pintype "passive"))
      (node (ref "UCA") (pin "P$25") (pinfunction "RC0*/AN6/DAC1RM_P$25") (pintype "bidirectional"))
    )
    (net (code "44") (name "/ENC_A_2") (class "Default")
      (node (ref "ENC2") (pin "5") (pinfunction "5_5") (pintype "passive"))
      (node (ref "UCA") (pin "P$36") (pinfunction "RC3*/PMBE_P$36") (pintype "bidirectional"))
    )
    (net (code "45") (name "/ENC_A_3") (class "Default")
      (node (ref "ENC3") (pin "5") (pinfunction "5_5") (pintype "passive"))
      (node (ref "UCB") (pin "P$38") (pinfunction "RC5*/PMA3_P$38") (pintype "bidirectional"))
    )
    (net (code "46") (name "/ENC_A_4") (class "Default")
      (node (ref "ENC4") (pin "5") (pinfunction "5_5") (pintype "passive"))
      (node (ref "UCB") (pin "P$1") (pinfunction "RB9*/SDA1/PMD3_P$1") (pintype "bidirectional"))
    )
    (net (code "47") (name "/ENC_B_1") (class "Default")
      (node (ref "ENC1") (pin "4") (pinfunction "4_4") (pintype "passive"))
      (node (ref "UCA") (pin "P$26") (pinfunction "RC1*/AN7/DAC1LM_P$26") (pintype "bidirectional"))
    )
    (net (code "48") (name "/ENC_B_2") (class "Default")
      (node (ref "ENC2") (pin "4") (pinfunction "4_4") (pintype "passive"))
      (node (ref "UCA") (pin "P$37") (pinfunction "RC4*/PMA4_P$37") (pintype "bidirectional"))
    )
    (net (code "49") (name "/ENC_B_3") (class "Default")
      (node (ref "ENC3") (pin "4") (pinfunction "4_4") (pintype "passive"))
      (node (ref "UCB") (pin "P$41") (pinfunction "RB5*/PGED3/ASDA1/PMD7_P$41") (pintype "bidirectional"))
    )
    (net (code "50") (name "/ENC_B_4") (class "Default")
      (node (ref "ENC4") (pin "4") (pinfunction "4_4") (pintype "passive"))
      (node (ref "UCB") (pin "P$4") (pinfunction "RC8*/PMA5_P$4") (pintype "bidirectional"))
    )
    (net (code "51") (name "/ENC_I_1") (class "Default")
      (node (ref "ENC1") (pin "2") (pinfunction "2_2") (pintype "passive"))
      (node (ref "UCA") (pin "P$27") (pinfunction "RC2*/AN8/CVREF/PMA2_P$27") (pintype "bidirectional"))
    )
    (net (code "52") (name "/ENC_I_2") (class "Default")
      (node (ref "ENC2") (pin "2") (pinfunction "2_2") (pintype "passive"))
      (node (ref "UCA") (pin "P$38") (pinfunction "RC5*/PMA3_P$38") (pintype "bidirectional"))
    )
    (net (code "53") (name "/ENC_I_3") (class "Default")
      (node (ref "ENC3") (pin "2") (pinfunction "2_2") (pintype "passive"))
      (node (ref "UCB") (pin "P$44") (pinfunction "RB8*/SCL1/PMD4_P$44") (pintype "bidirectional"))
    )
    (net (code "54") (name "/ENC_I_4") (class "Default")
      (node (ref "ENC4") (pin "2") (pinfunction "2_2") (pintype "passive"))
      (node (ref "UCB") (pin "P$5") (pinfunction "RC9*/PMA6_P$5") (pintype "bidirectional"))
    )
    (net (code "55") (name "/IA_1") (class "Default")
      (node (ref "IA_1") (pin "3") (pinfunction "3_3") (pintype "passive"))
      (node (ref "UCB") (pin "P$19") (pinfunction "RA0/AN0/VREF+/_P$19") (pintype "bidirectional"))
    )
    (net (code "56") (name "/IA_2") (class "Default")
      (node (ref "IA_2") (pin "3") (pinfunction "3_3") (pintype "passive"))
      (node (ref "UCB") (pin "P$20") (pinfunction "RA1/AN1/VREF-_P$20") (pintype "bidirectional"))
    )
    (net (code "57") (name "/IA_3") (class "Default")
      (node (ref "IA_3") (pin "3") (pinfunction "3_3") (pintype "passive"))
      (node (ref "UCB") (pin "P$13") (pinfunction "RA7/TCK/PMA7_P$13") (pintype "bidirectional"))
    )
    (net (code "58") (name "/IA_4") (class "Default")
      (node (ref "IA_4") (pin "3") (pinfunction "3_3") (pintype "passive"))
      (node (ref "UCB") (pin "P$32") (pinfunction "RA8/TDO/PMA8_P$32") (pintype "bidirectional"))
    )
    (net (code "59") (name "/IA_5") (class "Default")
      (node (ref "IA_5") (pin "3") (pinfunction "3_3") (pintype "passive"))
      (node (ref "UCB") (pin "P$35") (pinfunction "RA9/TDI/PMA9_P$35") (pintype "bidirectional"))
    )
    (net (code "60") (name "/IA_6") (class "Default")
      (node (ref "IA_6") (pin "3") (pinfunction "3_3") (pintype "passive"))
      (node (ref "UCB") (pin "P$12") (pinfunction "RA10/TMS/PMA10_P$12") (pintype "bidirectional"))
    )
    (net (code "61") (name "/IA_7") (class "Default")
      (node (ref "IA_7") (pin "3") (pinfunction "3_3") (pintype "passive"))
      (node (ref "UCB") (pin "P$25") (pinfunction "RC0*/AN6/DAC1RM_P$25") (pintype "bidirectional"))
    )
    (net (code "62") (name "/IA_8") (class "Default")
      (node (ref "IA_8") (pin "3") (pinfunction "3_3") (pintype "passive"))
      (node (ref "UCB") (pin "P$26") (pinfunction "RC1*/AN7/DAC1LM_P$26") (pintype "bidirectional"))
    )
    (net (code "63") (name "/IO_1") (class "Default")
      (node (ref "IO_1") (pin "3") (pinfunction "3_3") (pintype "passive"))
      (node (ref "UCA") (pin "P$23") (pinfunction "RB2*/AN4/C1IN-_P$23") (pintype "bidirectional"))
    )
    (net (code "64") (name "/IO_2") (class "Default")
      (node (ref "IO_2") (pin "3") (pinfunction "3_3") (pintype "passive"))
      (node (ref "UCA") (pin "P$24") (pinfunction "RB3*/AN5/C1IN+_P$24") (pintype "bidirectional"))
    )
    (net (code "65") (name "/IO_3") (class "Default")
      (node (ref "IO_3") (pin "3") (pinfunction "3_3") (pintype "passive"))
      (node (ref "UCA") (pin "P$33") (pinfunction "RB4*/SOSCI_P$33") (pintype "bidirectional"))
    )
    (net (code "66") (name "/IO_4") (class "Default")
      (node (ref "IO_4") (pin "3") (pinfunction "3_3") (pintype "passive"))
      (node (ref "UCB") (pin "P$33") (pinfunction "RB4*/SOSCI_P$33") (pintype "bidirectional"))
    )
    (net (code "67") (name "/IO_5") (class "Default")
      (node (ref "IO_5") (pin "3") (pinfunction "3_3") (pintype "passive"))
      (node (ref "UCA") (pin "P$30") (pinfunction "RA2/OSC1/CLKI_P$30") (pintype "bidirectional"))
    )
    (net (code "68") (name "/IO_6") (class "Default")
      (node (ref "IO_6") (pin "3") (pinfunction "3_3") (pintype "passive"))
      (node (ref "UCA") (pin "P$31") (pinfunction "RA3/OSC2/CLKO_P$31") (pintype "bidirectional"))
    )
    (net (code "69") (name "/IO_7") (class "Default")
      (node (ref "IO_7") (pin "3") (pinfunction "3_3") (pintype "passive"))
      (node (ref "UCB") (pin "P$36") (pinfunction "RC3*/PMBE_P$36") (pintype "bidirectional"))
    )
    (net (code "70") (name "/IO_8{slash}LED_B") (class "Default")
      (node (ref "IO_8") (pin "3") (pinfunction "3_3") (pintype "passive"))
      (node (ref "LED_B") (pin "C") (pinfunction "C_C") (pintype "passive"))
      (node (ref "UCB") (pin "P$37") (pinfunction "RC4*/PMA4_P$37") (pintype "bidirectional"))
    )
    (net (code "71") (name "/LED_A") (class "Default")
      (node (ref "LED_A") (pin "C") (pinfunction "C_C") (pintype "passive"))
      (node (ref "UCA") (pin "P$35") (pinfunction "RA9/TDI/PMA9_P$35") (pintype "bidirectional"))
    )
    (net (code "72") (name "/LED_RX") (class "Default")
      (node (ref "LED_RX") (pin "C") (pinfunction "C_C") (pintype "passive"))
      (node (ref "UFTDI") (pin "22") (pinfunction "RXLED_22") (pintype "bidirectional"))
    )
    (net (code "73") (name "/LED_TX") (class "Default")
      (node (ref "LED_TX") (pin "C") (pinfunction "C_C") (pintype "passive"))
      (node (ref "UFTDI") (pin "23") (pinfunction "TXLED_23") (pintype "bidirectional"))
    )
    (net (code "74") (name "/OSC1_B") (class "Default")
      (node (ref "CX1_B") (pin "1") (pinfunction "1_1") (pintype "bidirectional"))
      (node (ref "UCB") (pin "P$30") (pinfunction "RA2/OSC1/CLKI_P$30") (pintype "bidirectional"))
      (node (ref "XB") (pin "P$1") (pinfunction "1_P$1") (pintype "passive"))
    )
    (net (code "75") (name "/OSC2_B") (class "Default")
      (node (ref "CX2_B") (pin "1") (pinfunction "1_1") (pintype "bidirectional"))
      (node (ref "UCB") (pin "P$31") (pinfunction "RA3/OSC2/CLKO_P$31") (pintype "bidirectional"))
      (node (ref "XB") (pin "P$2") (pinfunction "2_P$2") (pintype "passive"))
    )
    (net (code "76") (name "/PGC_A") (class "Default")
      (node (ref "ICSP_A") (pin "5") (pinfunction "PGC_5") (pintype "passive"))
      (node (ref "UCA") (pin "P$22") (pinfunction "RB1*/PGEC1/AN3/C2IN+_P$22") (pintype "bidirectional"))
    )
    (net (code "77") (name "/PGC_B") (class "Default")
      (node (ref "ICSP_B") (pin "5") (pinfunction "PGC_5") (pintype "passive"))
      (node (ref "UCB") (pin "P$22") (pinfunction "RB1*/PGEC1/AN3/C2IN+_P$22") (pintype "bidirectional"))
    )
    (net (code "78") (name "/PGC_C") (class "Default")
      (node (ref "ICSP_C") (pin "5") (pinfunction "PGC_5") (pintype "passive"))
      (node (ref "UCC") (pin "11") (pinfunction "RA1/AN1/CPS1/C12IN0-/VREF+/SRI/RX/DT/ICSPCLK/ICDCLK_11") (pintype "bidirectional"))
    )
    (net (code "79") (name "/PGD_A") (class "Default")
      (node (ref "ICSP_A") (pin "4") (pinfunction "PGD_4") (pintype "passive"))
      (node (ref "UCA") (pin "P$21") (pinfunction "RB0*/PGED1/AN2/C2IN-_P$21") (pintype "bidirectional"))
    )
    (net (code "80") (name "/PGD_B") (class "Default")
      (node (ref "ICSP_B") (pin "4") (pinfunction "PGD_4") (pintype "passive"))
      (node (ref "UCB") (pin "P$21") (pinfunction "RB0*/PGED1/AN2/C2IN-_P$21") (pintype "bidirectional"))
    )
    (net (code "81") (name "/PGD_C") (class "Default")
      (node (ref "ICSP_C") (pin "4") (pinfunction "PGD_4") (pintype "passive"))
      (node (ref "UCC") (pin "12") (pinfunction "RA0/AN0/CPS0/C1IN+/VREF-/DACOUT/TX/CK/ICSPDAT/ICDDAT_12") (pintype "bidirectional"))
    )
    (net (code "82") (name "/SERVO_1") (class "Default")
      (node (ref "OPTO_1") (pin "10") (pinfunction "10_10") (pintype "bidirectional"))
      (node (ref "ROP_1") (pin "1") (pinfunction "1_1") (pintype "bidirectional"))
      (node (ref "SERVO1") (pin "3") (pinfunction "3_3") (pintype "passive"))
    )
    (net (code "83") (name "/SERVO_2") (class "Default")
      (node (ref "OPTO_1") (pin "12") (pinfunction "12_12") (pintype "bidirectional"))
      (node (ref "ROP_2") (pin "1") (pinfunction "1_1") (pintype "bidirectional"))
      (node (ref "SERVO2") (pin "3") (pinfunction "3_3") (pintype "passive"))
    )
    (net (code "84") (name "/SERVO_3") (class "Default")
      (node (ref "OPTO_1") (pin "14") (pinfunction "14_14") (pintype "bidirectional"))
      (node (ref "ROP_3") (pin "1") (pinfunction "1_1") (pintype "bidirectional"))
      (node (ref "SERVO3") (pin "3") (pinfunction "3_3") (pintype "passive"))
    )
    (net (code "85") (name "/SERVO_4") (class "Default")
      (node (ref "OPTO_1") (pin "16") (pinfunction "16_16") (pintype "bidirectional"))
      (node (ref "ROP_4") (pin "1") (pinfunction "1_1") (pintype "bidirectional"))
      (node (ref "SERVO4") (pin "3") (pinfunction "3_3") (pintype "passive"))
    )
    (net (code "86") (name "/SERVO_5") (class "Default")
      (node (ref "OPTO_2") (pin "16") (pinfunction "16_16") (pintype "bidirectional"))
      (node (ref "ROP_5") (pin "1") (pinfunction "1_1") (pintype "bidirectional"))
      (node (ref "SERVO5") (pin "3") (pinfunction "3_3") (pintype "passive"))
    )
    (net (code "87") (name "/SERVO_6") (class "Default")
      (node (ref "OPTO_2") (pin "14") (pinfunction "14_14") (pintype "bidirectional"))
      (node (ref "ROP_6") (pin "1") (pinfunction "1_1") (pintype "bidirectional"))
      (node (ref "SERVO6") (pin "3") (pinfunction "3_3") (pintype "passive"))
    )
    (net (code "88") (name "/SERVO_7") (class "Default")
      (node (ref "OPTO_2") (pin "12") (pinfunction "12_12") (pintype "bidirectional"))
      (node (ref "ROP_7") (pin "1") (pinfunction "1_1") (pintype "bidirectional"))
      (node (ref "SERVO7") (pin "3") (pinfunction "3_3") (pintype "passive"))
    )
    (net (code "89") (name "/SERVO_8") (class "Default")
      (node (ref "OPTO_2") (pin "10") (pinfunction "10_10") (pintype "bidirectional"))
      (node (ref "ROP_8") (pin "1") (pinfunction "1_1") (pintype "bidirectional"))
      (node (ref "SERVO8") (pin "3") (pinfunction "3_3") (pintype "passive"))
    )
    (net (code "90") (name "/SERVO_DIG_S") (class "Default")
      (node (ref "RSDIG") (pin "2") (pinfunction "2_2") (pintype "bidirectional"))
      (node (ref "SERVO_DIG_1") (pin "3") (pinfunction "3_3") (pintype "passive"))
      (node (ref "SERVO_DIG_2") (pin "3") (pinfunction "3_3") (pintype "passive"))
      (node (ref "UCB") (pin "P$27") (pinfunction "RC2*/AN8/CVREF/PMA2_P$27") (pintype "bidirectional"))
    )
    (net (code "91") (name "/SERVO_PWM_1") (class "Default")
      (node (ref "ROL_1") (pin "1") (pinfunction "1_1") (pintype "bidirectional"))
      (node (ref "UCC") (pin "1") (pinfunction "CCP2/P2A/T1CKI/T1OSI/OSC1/CLKIN/RA5_1") (pintype "bidirectional"))
    )
    (net (code "92") (name "/SERVO_PWM_2") (class "Default")
      (node (ref "ROL_2") (pin "1") (pinfunction "1_1") (pintype "bidirectional"))
      (node (ref "UCC") (pin "2") (pinfunction "T1G/P2B/SDO/CLKR/T1OSO/CLKOUT/OSC2/CPS3/AN3/RA4_2") (pintype "bidirectional"))
    )
    (net (code "93") (name "/SERVO_PWM_3") (class "Default")
      (node (ref "ROL_3") (pin "1") (pinfunction "1_1") (pintype "bidirectional"))
      (node (ref "UCC") (pin "5") (pinfunction "RC4/C2OUT/SRNQ/P1B/TX/CK/MDOUT_5") (pintype "bidirectional"))
    )
    (net (code "94") (name "/SERVO_PWM_4") (class "Default")
      (node (ref "ROL_4") (pin "1") (pinfunction "1_1") (pintype "bidirectional"))
      (node (ref "UCC") (pin "6") (pinfunction "RC3/AN7/CPS7/C12IN3-/P2A/CCP2/P1C/~{SS1}/MDMIN_6") (pintype "bidirectional"))
    )
    (net (code "95") (name "/SERVO_PWM_5") (class "Default")
      (node (ref "ROL_5") (pin "1") (pinfunction "1_1") (pintype "bidirectional"))
      (node (ref "UCC") (pin "7") (pinfunction "RC2/AN6/CPS6/C12IN2-/P1D/P2B/SDO/MDCIN1_7") (pintype "bidirectional"))
    )
    (net (code "96") (name "/SERVO_PWM_6") (class "Default")
      (node (ref "ROL_6") (pin "1") (pinfunction "1_1") (pintype "bidirectional"))
      (node (ref "UCC") (pin "8") (pinfunction "RC1/AN5/CPS5/C12IN1-/SDA/SDI/P1C/CCP4_8") (pintype "bidirectional"))
    )
    (net (code "97") (name "/SERVO_PWM_7") (class "Default")
      (node (ref "ROL_7") (pin "1") (pinfunction "1_1") (pintype "bidirectional"))
      (node (ref "UCC") (pin "9") (pinfunction "RC0/AN4/CPS4/C2IN+/SCL/SCK/P1D_9") (pintype "bidirectional"))
    )
    (net (code "98") (name "/SERVO_PWM_8{slash}LED_C") (class "Default")
      (node (ref "LED_C") (pin "C") (pinfunction "C_C") (pintype "passive"))
      (node (ref "ROL_8") (pin "1") (pinfunction "1_1") (pintype "bidirectional"))
      (node (ref "UCC") (pin "10") (pinfunction "RA2/AN2/CPS2/T0CKI/INT/C1OUT/SRQ/CCP3/FLT0_10") (pintype "bidirectional"))
    )
    (net (code "99") (name "/SM_+3V3_1") (class "Default")
      (node (ref "C3V3_STEP1") (pin "1") (pinfunction "1_1") (pintype "bidirectional"))
      (node (ref "RDECAY1_SM1") (pin "2") (pinfunction "2_2") (pintype "bidirectional"))
      (node (ref "RREF1_SM1") (pin "2") (pinfunction "2_2") (pintype "bidirectional"))
      (node (ref "STEP_DRIVER_1") (pin "P$15") (pinfunction "V3P3OUT_P$15") (pintype "bidirectional"))
    )
    (net (code "100") (name "/SM_AOUT1_1") (class "Default")
      (node (ref "STEP1") (pin "4") (pinfunction "4_4") (pintype "passive"))
      (node (ref "STEP_DRIVER_1") (pin "P$5") (pinfunction "AOUT1_P$5") (pintype "bidirectional"))
    )
    (net (code "101") (name "/SM_AOUT2_1") (class "Default")
      (node (ref "STEP1") (pin "3") (pinfunction "3_3") (pintype "passive"))
      (node (ref "STEP_DRIVER_1") (pin "P$7") (pinfunction "AOUT2_P$7") (pintype "bidirectional"))
    )
    (net (code "102") (name "/SM_BOUT1_1") (class "Default")
      (node (ref "STEP1") (pin "1") (pinfunction "1_1") (pintype "passive"))
      (node (ref "STEP_DRIVER_1") (pin "P$10") (pinfunction "BOUT1_P$10") (pintype "bidirectional"))
    )
    (net (code "103") (name "/SM_BOUT2_1") (class "Default")
      (node (ref "STEP1") (pin "2") (pinfunction "2_2") (pintype "passive"))
      (node (ref "STEP_DRIVER_1") (pin "P$8") (pinfunction "BOUT2_P$8") (pintype "bidirectional"))
    )
    (net (code "104") (name "/SM_DECAY_1") (class "Default")
      (node (ref "RDECAY1_SM1") (pin "1") (pinfunction "1_1") (pintype "bidirectional"))
      (node (ref "RDECAY2_SM1") (pin "2") (pinfunction "2_2") (pintype "bidirectional"))
      (node (ref "STEP_DRIVER_1") (pin "P$19") (pinfunction "DECAY_P$19") (pintype "bidirectional"))
    )
    (net (code "105") (name "/SM_DIR_1") (class "Default")
      (node (ref "STEP_DRIVER_1") (pin "P$20") (pinfunction "DIR_P$20") (pintype "bidirectional"))
      (node (ref "UCA") (pin "P$19") (pinfunction "RA0/AN0/VREF+/_P$19") (pintype "bidirectional"))
    )
    (net (code "106") (name "/SM_STEP_1") (class "Default")
      (node (ref "STEP_DRIVER_1") (pin "P$22") (pinfunction "STEP_P$22") (pintype "bidirectional"))
      (node (ref "UCA") (pin "P$4") (pinfunction "RC8*/PMA5_P$4") (pintype "bidirectional"))
    )
    (net (code "107") (name "/SM_VREF_1") (class "Default")
      (node (ref "RREF1_SM1") (pin "1") (pinfunction "1_1") (pintype "bidirectional"))
      (node (ref "RREF2_SM1") (pin "2") (pinfunction "2_2") (pintype "bidirectional"))
      (node (ref "STEP_DRIVER_1") (pin "P$12") (pinfunction "AVREF_P$12") (pintype "bidirectional"))
      (node (ref "STEP_DRIVER_1") (pin "P$13") (pinfunction "BVREF_P$13") (pintype "bidirectional"))
    )
    (net (code "108") (name "/SM_~{HOME}_1") (class "Default")
      (node (ref "RHOME_SM1") (pin "1") (pinfunction "1_1") (pintype "bidirectional"))
      (node (ref "STEP_DRIVER_1") (pin "P$27") (pinfunction "~{HOME}_P$27") (pintype "bidirectional"))
      (node (ref "UCA") (pin "P$20") (pinfunction "RA1/AN1/VREF-_P$20") (pintype "bidirectional"))
    )
    (net (code "109") (name "/SM_~{RESET}") (class "Default")
      (node (ref "STEP_DRIVER_1") (pin "P$16") (pinfunction "~{RESET}_P$16") (pintype "bidirectional"))
      (node (ref "UCA") (pin "P$32") (pinfunction "RA8/TDO/PMA8_P$32") (pintype "bidirectional"))
    )
    (net (code "110") (name "/SPARE_IO_1") (class "Default")
      (node (ref "UCA") (pin "P$13") (pinfunction "RA7/TCK/PMA7_P$13") (pintype "bidirectional"))
    )
    (net (code "111") (name "/SPARE_IO_2") (class "Default")
      (node (ref "UCA") (pin "P$12") (pinfunction "RA10/TMS/PMA10_P$12") (pintype "bidirectional"))
    )
    (net (code "112") (name "/SPARE_IO_3") (class "Default")
      (node (ref "UCA") (pin "P$5") (pinfunction "RC9*/PMA6_P$5") (pintype "bidirectional"))
    )
    (net (code "113") (name "/UART_RX") (class "Default")
      (node (ref "JP_URX") (pin "2") (pinfunction "2_2") (pintype "passive"))
      (node (ref "UFTDI") (pin "5") (pinfunction "RXD_5") (pintype "input"))
    )
    (net (code "114") (name "/UART_RX_A") (class "Default")
      (node (ref "JP_URX") (pin "1") (pinfunction "1_1") (pintype "passive"))
      (node (ref "UCA") (pin "P$44") (pinfunction "RB8*/SCL1/PMD4_P$44") (pintype "bidirectional"))
    )
    (net (code "115") (name "/UART_RX_B") (class "Default")
      (node (ref "JP_URX") (pin "3") (pinfunction "3_3") (pintype "passive"))
      (node (ref "UCB") (pin "P$23") (pinfunction "RB2*/AN4/C1IN-_P$23") (pintype "bidirectional"))
    )
    (net (code "116") (name "/UART_RX_C") (class "Default")
      (node (ref "UCA") (pin "P$41") (pinfunction "RB5*/PGED3/ASDA1/PMD7_P$41") (pintype "bidirectional"))
      (node (ref "UCC") (pin "4") (pinfunction "MDCIN2/DT/RX/CCP1/P1A/RC5_4") (pintype "bidirectional"))
    )
    (net (code "117") (name "/UART_TX") (class "Default")
      (node (ref "JP_UTX") (pin "2") (pinfunction "2_2") (pintype "passive"))
      (node (ref "UFTDI") (pin "1") (pinfunction "TXD_1") (pintype "output"))
    )
    (net (code "118") (name "/UART_TX_A") (class "Default")
      (node (ref "JP_UTX") (pin "1") (pinfunction "1_1") (pintype "passive"))
      (node (ref "UCA") (pin "P$1") (pinfunction "RB9*/SDA1/PMD3_P$1") (pintype "bidirectional"))
    )
    (net (code "119") (name "/UART_TX_B") (class "Default")
      (node (ref "JP_UTX") (pin "3") (pinfunction "3_3") (pintype "passive"))
      (node (ref "UCB") (pin "P$24") (pinfunction "RB3*/AN5/C1IN+_P$24") (pintype "bidirectional"))
    )
    (net (code "120") (name "/USBDM") (class "Default")
      (node (ref "UFTDI") (pin "16") (pinfunction "USBDM_16") (pintype "bidirectional"))
      (node (ref "X1") (pin "D-") (pinfunction "D-_D-") (pintype "bidirectional"))
    )
    (net (code "121") (name "/USBDP") (class "Default")
      (node (ref "UFTDI") (pin "15") (pinfunction "USBDP_15") (pintype "bidirectional"))
      (node (ref "X1") (pin "D+") (pinfunction "D+_D+") (pintype "bidirectional"))
    )
    (net (code "122") (name "/VCAP_A") (class "Default")
      (node (ref "CCAP_A") (pin "1") (pinfunction "1_1") (pintype "passive"))
      (node (ref "UCA") (pin "P$7") (pinfunction "VCAP_P$7") (pintype "bidirectional"))
    )
    (net (code "123") (name "/VCAP_B") (class "Default")
      (node (ref "CCAP_B") (pin "1") (pinfunction "1_1") (pintype "passive"))
      (node (ref "UCB") (pin "P$7") (pinfunction "VCAP_P$7") (pintype "bidirectional"))
    )
    (net (code "124") (name "/~{MCLR}_A") (class "Default")
      (node (ref "ICSP_A") (pin "1") (pinfunction "VPP_1") (pintype "passive"))
      (node (ref "JPRST_A") (pin "1") (pinfunction "1_1") (pintype "passive"))
      (node (ref "RMCLR_A") (pin "2") (pinfunction "2_2") (pintype "bidirectional"))
      (node (ref "UCA") (pin "P$18") (pinfunction "~{MCLR}_P$18") (pintype "bidirectional"))
    )
    (net (code "125") (name "/~{MCLR}_B") (class "Default")
      (node (ref "ICSP_B") (pin "1") (pinfunction "VPP_1") (pintype "passive"))
      (node (ref "JPRST_B") (pin "1") (pinfunction "1_1") (pintype "passive"))
      (node (ref "RMCLR_B") (pin "2") (pinfunction "2_2") (pintype "bidirectional"))
      (node (ref "UCB") (pin "P$18") (pinfunction "~{MCLR}_P$18") (pintype "bidirectional"))
    )
    (net (code "126") (name "/~{MCLR}_C") (class "Default")
      (node (ref "ICSP_C") (pin "1") (pinfunction "VPP_1") (pintype "passive"))
      (node (ref "JPRST_C") (pin "1") (pinfunction "1_1") (pintype "passive"))
      (node (ref "RMCLR_C") (pin "2") (pinfunction "2_2") (pintype "bidirectional"))
      (node (ref "UCC") (pin "3") (pinfunction "~{MCLR}/VPP/T1G/~{SS1}/RA3_3") (pintype "bidirectional"))
    )
    (net (code "127") (name "/~{RESET}") (class "Default")
      (node (ref "FDP_BOT") (pin "P$5") (pinfunction "P$5_P$5") (pintype "bidirectional"))
      (node (ref "JPRST_A") (pin "2") (pinfunction "2_2") (pintype "passive"))
      (node (ref "JPRST_B") (pin "2") (pinfunction "2_2") (pintype "passive"))
      (node (ref "JPRST_C") (pin "2") (pinfunction "2_2") (pintype "passive"))
    )
    (net (code "128") (name "3.3V") (class "Default")
      (node (ref "C1") (pin "+") (pinfunction "+_+") (pintype "passive"))
      (node (ref "CAN_DRV_A") (pin "3") (pinfunction "VDD_3") (pintype "bidirectional"))
      (node (ref "CAN_DRV_B") (pin "3") (pinfunction "VDD_3") (pintype "bidirectional"))
      (node (ref "CDEC_A_1") (pin "1") (pinfunction "1_1") (pintype "bidirectional"))
      (node (ref "CDEC_A_2") (pin "1") (pinfunction "1_1") (pintype "bidirectional"))
      (node (ref "CDEC_A_3") (pin "1") (pinfunction "1_1") (pintype "bidirectional"))
      (node (ref "CDEC_B_1") (pin "1") (pinfunction "1_1") (pintype "bidirectional"))
      (node (ref "CDEC_B_2") (pin "1") (pinfunction "1_1") (pintype "bidirectional"))
      (node (ref "CDEC_B_3") (pin "1") (pinfunction "1_1") (pintype "bidirectional"))
      (node (ref "CDEC_C") (pin "1") (pinfunction "1_1") (pintype "bidirectional"))
      (node (ref "CDEC_CAN_A") (pin "1") (pinfunction "1_1") (pintype "bidirectional"))
      (node (ref "CDEC_CAN_B") (pin "1") (pinfunction "1_1") (pintype "bidirectional"))
      (node (ref "CDEC_FTDI1") (pin "1") (pinfunction "1_1") (pintype "bidirectional"))
      (node (ref "CDEC_FTDI2") (pin "1") (pinfunction "1_1") (pintype "bidirectional"))
      (node (ref "ICSP_A") (pin "2") (pinfunction "VCC_2") (pintype "passive"))
      (node (ref "ICSP_B") (pin "2") (pinfunction "VCC_2") (pintype "passive"))
      (node (ref "ICSP_C") (pin "2") (pinfunction "VCC_2") (pintype "passive"))
      (node (ref "IO_1") (pin "2") (pinfunction "2_2") (pintype "passive"))
      (node (ref "IO_2") (pin "2") (pinfunction "2_2") (pintype "passive"))
      (node (ref "IO_3") (pin "2") (pinfunction "2_2") (pintype "passive"))
      (node (ref "IO_4") (pin "2") (pinfunction "2_2") (pintype "passive"))
      (node (ref "IO_5") (pin "2") (pinfunction "2_2") (pintype "passive"))
      (node (ref "IO_6") (pin "2") (pinfunction "2_2") (pintype "passive"))
      (node (ref "IO_7") (pin "2") (pinfunction "2_2") (pintype "passive"))
      (node (ref "IO_8") (pin "2") (pinfunction "2_2") (pintype "passive"))
      (node (ref "R1_DC1") (pin "1") (pinfunction "1_1") (pintype "bidirectional"))
      (node (ref "R1_DC2") (pin "1") (pinfunction "1_1") (pintype "bidirectional"))
      (node (ref "R1_DC3") (pin "1") (pinfunction "1_1") (pintype "bidirectional"))
      (node (ref "R1_DC4") (pin "1") (pinfunction "1_1") (pintype "bidirectional"))
      (node (ref "R1_DC5") (pin "1") (pinfunction "1_1") (pintype "bidirectional"))
      (node (ref "R1_DC6") (pin "1") (pinfunction "1_1") (pintype "bidirectional"))
      (node (ref "R1_DC7") (pin "1") (pinfunction "1_1") (pintype "bidirectional"))
      (node (ref "R1_DC8") (pin "1") (pinfunction "1_1") (pintype "bidirectional"))
      (node (ref "R2_DC1") (pin "1") (pinfunction "1_1") (pintype "bidirectional"))
      (node (ref "R2_DC2") (pin "1") (pinfunction "1_1") (pintype "bidirectional"))
      (node (ref "R2_DC3") (pin "1") (pinfunction "1_1") (pintype "bidirectional"))
      (node (ref "R2_DC4") (pin "1") (pinfunction "1_1") (pintype "bidirectional"))
      (node (ref "R2_DC5") (pin "1") (pinfunction "1_1") (pintype "bidirectional"))
      (node (ref "R2_DC6") (pin "1") (pinfunction "1_1") (pintype "bidirectional"))
      (node (ref "R2_DC7") (pin "1") (pinfunction "1_1") (pintype "bidirectional"))
      (node (ref "R2_DC8") (pin "1") (pinfunction "1_1") (pintype "bidirectional"))
      (node (ref "REG_3_3V") (pin "5") (pinfunction "VOUT_5") (pintype "bidirectional"))
      (node (ref "RHOME_SM1") (pin "2") (pinfunction "2_2") (pintype "bidirectional"))
      (node (ref "RLA") (pin "1") (pinfunction "1_1") (pintype "bidirectional"))
      (node (ref "RLB") (pin "1") (pinfunction "1_1") (pintype "bidirectional"))
      (node (ref "RLC") (pin "1") (pinfunction "1_1") (pintype "bidirectional"))
      (node (ref "RLRX") (pin "1") (pinfunction "1_1") (pintype "bidirectional"))
      (node (ref "RLTX") (pin "1") (pinfunction "1_1") (pintype "bidirectional"))
      (node (ref "RMCLR_A") (pin "1") (pinfunction "1_1") (pintype "bidirectional"))
      (node (ref "RMCLR_B") (pin "1") (pinfunction "1_1") (pintype "bidirectional"))
      (node (ref "RMCLR_C") (pin "1") (pinfunction "1_1") (pintype "bidirectional"))
      (node (ref "RSDIG") (pin "1") (pinfunction "1_1") (pintype "bidirectional"))
      (node (ref "STEP_DRIVER_1") (pin "P$17") (pinfunction "~{SLEEP}_P$17") (pintype "bidirectional"))
      (node (ref "STEP_DRIVER_1") (pin "P$24") (pinfunction "MODE0_P$24") (pintype "bidirectional"))
      (node (ref "STEP_DRIVER_1") (pin "P$25") (pinfunction "MODE1_P$25") (pintype "bidirectional"))
      (node (ref "STEP_DRIVER_1") (pin "P$26") (pinfunction "MODE2_P$26") (pintype "bidirectional"))
      (node (ref "UCA") (pin "P$17") (pinfunction "AVDD_P$17") (pintype "bidirectional"))
      (node (ref "UCA") (pin "P$28") (pinfunction "VDD1_P$28") (pintype "bidirectional"))
      (node (ref "UCA") (pin "P$40") (pinfunction "VDD2_P$40") (pintype "bidirectional"))
      (node (ref "UCB") (pin "P$17") (pinfunction "AVDD_P$17") (pintype "bidirectional"))
      (node (ref "UCB") (pin "P$28") (pinfunction "VDD1_P$28") (pintype "bidirectional"))
      (node (ref "UCB") (pin "P$40") (pinfunction "VDD2_P$40") (pintype "bidirectional"))
      (node (ref "UCC") (pin "16") (pinfunction "VDD_16") (pintype "bidirectional"))
      (node (ref "UFTDI") (pin "20") (pinfunction "VCC_20") (pintype "power_in"))
      (node (ref "UFTDI") (pin "4") (pinfunction "VCCIO_4") (pintype "power_in"))
    )
    (net (code "129") (name "GND") (class "Default")
      (node (ref "C1") (pin "-") (pinfunction "-_-") (pintype "passive"))
      (node (ref "C3V3_STEP1") (pin "2") (pinfunction "2_2") (pintype "bidirectional"))
      (node (ref "CAN_DRV_A") (pin "2") (pinfunction "GND_2") (pintype "bidirectional"))
      (node (ref "CAN_DRV_B") (pin "2") (pinfunction "GND_2") (pintype "bidirectional"))
      (node (ref "CCAP_A") (pin "2") (pinfunction "2_2") (pintype "passive"))
      (node (ref "CCAP_B") (pin "2") (pinfunction "2_2") (pintype "passive"))
      (node (ref "CDEC_A_1") (pin "2") (pinfunction "2_2") (pintype "bidirectional"))
      (node (ref "CDEC_A_2") (pin "2") (pinfunction "2_2") (pintype "bidirectional"))
      (node (ref "CDEC_A_3") (pin "2") (pinfunction "2_2") (pintype "bidirectional"))
      (node (ref "CDEC_B_1") (pin "2") (pinfunction "2_2") (pintype "bidirectional"))
      (node (ref "CDEC_B_2") (pin "2") (pinfunction "2_2") (pintype "bidirectional"))
      (node (ref "CDEC_B_3") (pin "2") (pinfunction "2_2") (pintype "bidirectional"))
      (node (ref "CDEC_C") (pin "2") (pinfunction "2_2") (pintype "bidirectional"))
      (node (ref "CDEC_CAN_A") (pin "2") (pinfunction "2_2") (pintype "bidirectional"))
      (node (ref "CDEC_CAN_B") (pin "2") (pinfunction "2_2") (pintype "bidirectional"))
      (node (ref "CDEC_FTDI1") (pin "2") (pinfunction "2_2") (pintype "bidirectional"))
      (node (ref "CDEC_FTDI2") (pin "2") (pinfunction "2_2") (pintype "bidirectional"))
      (node (ref "CS1_DC1") (pin "-") (pinfunction "-_-") (pintype "passive"))
      (node (ref "CS1_DC2") (pin "-") (pinfunction "-_-") (pintype "passive"))
      (node (ref "CS1_DC3") (pin "-") (pinfunction "-_-") (pintype "passive"))
      (node (ref "CS1_DC4") (pin "-") (pinfunction "-_-") (pintype "passive"))
      (node (ref "CS1_DC5") (pin "-") (pinfunction "-_-") (pintype "passive"))
      (node (ref "CS1_DC6") (pin "-") (pinfunction "-_-") (pintype "passive"))
      (node (ref "CS1_DC7") (pin "-") (pinfunction "-_-") (pintype "passive"))
      (node (ref "CS1_DC8") (pin "-") (pinfunction "-_-") (pintype "passive"))
      (node (ref "CS2_DC1") (pin "1") (pinfunction "1_1") (pintype "bidirectional"))
      (node (ref "CS2_DC2") (pin "1") (pinfunction "1_1") (pintype "bidirectional"))
      (node (ref "CS2_DC3") (pin "1") (pinfunction "1_1") (pintype "bidirectional"))
      (node (ref "CS2_DC4") (pin "1") (pinfunction "1_1") (pintype "bidirectional"))
      (node (ref "CS2_DC5") (pin "1") (pinfunction "1_1") (pintype "bidirectional"))
      (node (ref "CS2_DC6") (pin "1") (pinfunction "1_1") (pintype "bidirectional"))
      (node (ref "CS2_DC7") (pin "1") (pinfunction "1_1") (pintype "bidirectional"))
      (node (ref "CS2_DC8") (pin "1") (pinfunction "1_1") (pintype "bidirectional"))
      (node (ref "CX1_B") (pin "2") (pinfunction "2_2") (pintype "bidirectional"))
      (node (ref "CX2_B") (pin "2") (pinfunction "2_2") (pintype "bidirectional"))
      (node (ref "DRV_DC1") (pin "12") (pinfunction "GND2_12") (pintype "bidirectional"))
      (node (ref "DRV_DC1") (pin "2") (pinfunction "GND1_2") (pintype "bidirectional"))
      (node (ref "DRV_DC1") (pin "5") (pinfunction "MODE2_5") (pintype "bidirectional"))
      (node (ref "DRV_DC1") (pin "7") (pinfunction "SENSE_7") (pintype "bidirectional"))
      (node (ref "DRV_DC1") (pin "TH") (pinfunction "PAD_TH") (pintype "bidirectional"))
      (node (ref "DRV_DC2") (pin "12") (pinfunction "GND2_12") (pintype "bidirectional"))
      (node (ref "DRV_DC2") (pin "2") (pinfunction "GND1_2") (pintype "bidirectional"))
      (node (ref "DRV_DC2") (pin "5") (pinfunction "MODE2_5") (pintype "bidirectional"))
      (node (ref "DRV_DC2") (pin "7") (pinfunction "SENSE_7") (pintype "bidirectional"))
      (node (ref "DRV_DC2") (pin "TH") (pinfunction "PAD_TH") (pintype "bidirectional"))
      (node (ref "DRV_DC3") (pin "12") (pinfunction "GND2_12") (pintype "bidirectional"))
      (node (ref "DRV_DC3") (pin "2") (pinfunction "GND1_2") (pintype "bidirectional"))
      (node (ref "DRV_DC3") (pin "5") (pinfunction "MODE2_5") (pintype "bidirectional"))
      (node (ref "DRV_DC3") (pin "7") (pinfunction "SENSE_7") (pintype "bidirectional"))
      (node (ref "DRV_DC3") (pin "TH") (pinfunction "PAD_TH") (pintype "bidirectional"))
      (node (ref "DRV_DC4") (pin "12") (pinfunction "GND2_12") (pintype "bidirectional"))
      (node (ref "DRV_DC4") (pin "2") (pinfunction "GND1_2") (pintype "bidirectional"))
      (node (ref "DRV_DC4") (pin "5") (pinfunction "MODE2_5") (pintype "bidirectional"))
      (node (ref "DRV_DC4") (pin "7") (pinfunction "SENSE_7") (pintype "bidirectional"))
      (node (ref "DRV_DC4") (pin "TH") (pinfunction "PAD_TH") (pintype "bidirectional"))
      (node (ref "DRV_DC5") (pin "12") (pinfunction "GND2_12") (pintype "bidirectional"))
      (node (ref "DRV_DC5") (pin "2") (pinfunction "GND1_2") (pintype "bidirectional"))
      (node (ref "DRV_DC5") (pin "5") (pinfunction "MODE2_5") (pintype "bidirectional"))
      (node (ref "DRV_DC5") (pin "7") (pinfunction "SENSE_7") (pintype "bidirectional"))
      (node (ref "DRV_DC5") (pin "TH") (pinfunction "PAD_TH") (pintype "bidirectional"))
      (node (ref "DRV_DC6") (pin "12") (pinfunction "GND2_12") (pintype "bidirectional"))
      (node (ref "DRV_DC6") (pin "2") (pinfunction "GND1_2") (pintype "bidirectional"))
      (node (ref "DRV_DC6") (pin "5") (pinfunction "MODE2_5") (pintype "bidirectional"))
      (node (ref "DRV_DC6") (pin "7") (pinfunction "SENSE_7") (pintype "bidirectional"))
      (node (ref "DRV_DC6") (pin "TH") (pinfunction "PAD_TH") (pintype "bidirectional"))
      (node (ref "DRV_DC7") (pin "12") (pinfunction "GND2_12") (pintype "bidirectional"))
      (node (ref "DRV_DC7") (pin "2") (pinfunction "GND1_2") (pintype "bidirectional"))
      (node (ref "DRV_DC7") (pin "5") (pinfunction "MODE2_5") (pintype "bidirectional"))
      (node (ref "DRV_DC7") (pin "7") (pinfunction "SENSE_7") (pintype "bidirectional"))
      (node (ref "DRV_DC7") (pin "TH") (pinfunction "PAD_TH") (pintype "bidirectional"))
      (node (ref "DRV_DC8") (pin "12") (pinfunction "GND2_12") (pintype "bidirectional"))
      (node (ref "DRV_DC8") (pin "2") (pinfunction "GND1_2") (pintype "bidirectional"))
      (node (ref "DRV_DC8") (pin "5") (pinfunction "MODE2_5") (pintype "bidirectional"))
      (node (ref "DRV_DC8") (pin "7") (pinfunction "SENSE_7") (pintype "bidirectional"))
      (node (ref "DRV_DC8") (pin "TH") (pinfunction "PAD_TH") (pintype "bidirectional"))
      (node (ref "ENC1") (pin "1") (pinfunction "1_1") (pintype "passive"))
      (node (ref "ENC2") (pin "1") (pinfunction "1_1") (pintype "passive"))
      (node (ref "ENC3") (pin "1") (pinfunction "1_1") (pintype "passive"))
      (node (ref "ENC4") (pin "1") (pinfunction "1_1") (pintype "passive"))
      (node (ref "FDP_BOT") (pin "P$10") (pinfunction "P$10_P$10") (pintype "bidirectional"))
      (node (ref "FDP_BOT") (pin "P$12") (pinfunction "P$12_P$12") (pintype "bidirectional"))
      (node (ref "FDP_BOT") (pin "P$14") (pinfunction "P$14_P$14") (pintype "bidirectional"))
      (node (ref "FDP_BOT") (pin "P$16") (pinfunction "P$16_P$16") (pintype "bidirectional"))
      (node (ref "FDP_BOT") (pin "P$18") (pinfunction "P$18_P$18") (pintype "bidirectional"))
      (node (ref "FDP_BOT") (pin "P$2") (pinfunction "P$2_P$2") (pintype "bidirectional"))
      (node (ref "FDP_BOT") (pin "P$20") (pinfunction "P$20_P$20") (pintype "bidirectional"))
      (node (ref "FDP_BOT") (pin "P$22") (pinfunction "P$22_P$22") (pintype "bidirectional"))
      (node (ref "FDP_BOT") (pin "P$24") (pinfunction "P$24_P$24") (pintype "bidirectional"))
      (node (ref "FDP_BOT") (pin "P$26") (pinfunction "P$26_P$26") (pintype "bidirectional"))
      (node (ref "FDP_BOT") (pin "P$8") (pinfunction "P$8_P$8") (pintype "bidirectional"))
      (node (ref "FDP_TOP") (pin "P$10") (pinfunction "P$10_P$10") (pintype "bidirectional"))
      (node (ref "FDP_TOP") (pin "P$12") (pinfunction "P$12_P$12") (pintype "bidirectional"))
      (node (ref "FDP_TOP") (pin "P$14") (pinfunction "P$14_P$14") (pintype "bidirectional"))
      (node (ref "FDP_TOP") (pin "P$16") (pinfunction "P$16_P$16") (pintype "bidirectional"))
      (node (ref "FDP_TOP") (pin "P$18") (pinfunction "P$18_P$18") (pintype "bidirectional"))
      (node (ref "FDP_TOP") (pin "P$2") (pinfunction "P$2_P$2") (pintype "bidirectional"))
      (node (ref "FDP_TOP") (pin "P$20") (pinfunction "P$20_P$20") (pintype "bidirectional"))
      (node (ref "FDP_TOP") (pin "P$22") (pinfunction "P$22_P$22") (pintype "bidirectional"))
      (node (ref "FDP_TOP") (pin "P$24") (pinfunction "P$24_P$24") (pintype "bidirectional"))
      (node (ref "FDP_TOP") (pin "P$26") (pinfunction "P$26_P$26") (pintype "bidirectional"))
      (node (ref "FDP_TOP") (pin "P$8") (pinfunction "P$8_P$8") (pintype "bidirectional"))
      (node (ref "IA_1") (pin "1") (pinfunction "1_1") (pintype "passive"))
      (node (ref "IA_2") (pin "1") (pinfunction "1_1") (pintype "passive"))
      (node (ref "IA_3") (pin "1") (pinfunction "1_1") (pintype "passive"))
      (node (ref "IA_4") (pin "1") (pinfunction "1_1") (pintype "passive"))
      (node (ref "IA_5") (pin "1") (pinfunction "1_1") (pintype "passive"))
      (node (ref "IA_6") (pin "1") (pinfunction "1_1") (pintype "passive"))
      (node (ref "IA_7") (pin "1") (pinfunction "1_1") (pintype "passive"))
      (node (ref "IA_8") (pin "1") (pinfunction "1_1") (pintype "passive"))
      (node (ref "ICSP_A") (pin "3") (pinfunction "GND_3") (pintype "passive"))
      (node (ref "ICSP_B") (pin "3") (pinfunction "GND_3") (pintype "passive"))
      (node (ref "ICSP_C") (pin "3") (pinfunction "GND_3") (pintype "passive"))
      (node (ref "IO_1") (pin "1") (pinfunction "1_1") (pintype "passive"))
      (node (ref "IO_2") (pin "1") (pinfunction "1_1") (pintype "passive"))
      (node (ref "IO_3") (pin "1") (pinfunction "1_1") (pintype "passive"))
      (node (ref "IO_4") (pin "1") (pinfunction "1_1") (pintype "passive"))
      (node (ref "IO_5") (pin "1") (pinfunction "1_1") (pintype "passive"))
      (node (ref "IO_6") (pin "1") (pinfunction "1_1") (pintype "passive"))
      (node (ref "IO_7") (pin "1") (pinfunction "1_1") (pintype "passive"))
      (node (ref "IO_8") (pin "1") (pinfunction "1_1") (pintype "passive"))
      (node (ref "JP_GND") (pin "1") (pinfunction "1_1") (pintype "passive"))
      (node (ref "JP_GND") (pin "2") (pinfunction "2_2") (pintype "passive"))
      (node (ref "OPTO_1") (pin "11") (pinfunction "11_11") (pintype "bidirectional"))
      (node (ref "OPTO_1") (pin "13") (pinfunction "13_13") (pintype "bidirectional"))
      (node (ref "OPTO_1") (pin "15") (pinfunction "15_15") (pintype "bidirectional"))
      (node (ref "OPTO_1") (pin "2") (pinfunction "2_2") (pintype "bidirectional"))
      (node (ref "OPTO_1") (pin "4") (pinfunction "4_4") (pintype "bidirectional"))
      (node (ref "OPTO_1") (pin "6") (pinfunction "6_6") (pintype "bidirectional"))
      (node (ref "OPTO_1") (pin "8") (pinfunction "8_8") (pintype "bidirectional"))
      (node (ref "OPTO_1") (pin "9") (pinfunction "9_9") (pintype "bidirectional"))
      (node (ref "OPTO_2") (pin "11") (pinfunction "11_11") (pintype "bidirectional"))
      (node (ref "OPTO_2") (pin "13") (pinfunction "13_13") (pintype "bidirectional"))
      (node (ref "OPTO_2") (pin "15") (pinfunction "15_15") (pintype "bidirectional"))
      (node (ref "OPTO_2") (pin "2") (pinfunction "2_2") (pintype "bidirectional"))
      (node (ref "OPTO_2") (pin "4") (pinfunction "4_4") (pintype "bidirectional"))
      (node (ref "OPTO_2") (pin "6") (pinfunction "6_6") (pintype "bidirectional"))
      (node (ref "OPTO_2") (pin "8") (pinfunction "8_8") (pintype "bidirectional"))
      (node (ref "OPTO_2") (pin "9") (pinfunction "9_9") (pintype "bidirectional"))
      (node (ref "RDECAY2_SM1") (pin "1") (pinfunction "1_1") (pintype "bidirectional"))
      (node (ref "REG_3_3V") (pin "2") (pinfunction "GND_2") (pintype "bidirectional"))
      (node (ref "RISENA_SM1") (pin "2") (pinfunction "2_2") (pintype "bidirectional"))
      (node (ref "RISENB_SM1") (pin "2") (pinfunction "2_2") (pintype "bidirectional"))
      (node (ref "RREF2_SM1") (pin "1") (pinfunction "1_1") (pintype "bidirectional"))
      (node (ref "RS_CAN_A") (pin "1") (pinfunction "1_1") (pintype "bidirectional"))
      (node (ref "RS_CAN_B") (pin "1") (pinfunction "1_1") (pintype "bidirectional"))
      (node (ref "SERVO1") (pin "1") (pinfunction "1_1") (pintype "passive"))
      (node (ref "SERVO2") (pin "1") (pinfunction "1_1") (pintype "passive"))
      (node (ref "SERVO3") (pin "1") (pinfunction "1_1") (pintype "passive"))
      (node (ref "SERVO4") (pin "1") (pinfunction "1_1") (pintype "passive"))
      (node (ref "SERVO5") (pin "1") (pinfunction "1_1") (pintype "passive"))
      (node (ref "SERVO6") (pin "1") (pinfunction "1_1") (pintype "passive"))
      (node (ref "SERVO7") (pin "1") (pinfunction "1_1") (pintype "passive"))
      (node (ref "SERVO8") (pin "1") (pinfunction "1_1") (pintype "passive"))
      (node (ref "SERVO_DIG_1") (pin "1") (pinfunction "1_1") (pintype "passive"))
      (node (ref "SERVO_DIG_2") (pin "1") (pinfunction "1_1") (pintype "passive"))
      (node (ref "STEP_DRIVER_1") (pin "P$14") (pinfunction "GND1_P$14") (pintype "bidirectional"))
      (node (ref "STEP_DRIVER_1") (pin "P$21") (pinfunction "~{ENABLE}_P$21") (pintype "bidirectional"))
      (node (ref "STEP_DRIVER_1") (pin "P$28") (pinfunction "GND2_P$28") (pintype "bidirectional"))
      (node (ref "STEP_DRIVER_1") (pin "PAD") (pinfunction "PAD_PAD") (pintype "bidirectional"))
      (node (ref "UCA") (pin "P$16") (pinfunction "AVSS_P$16") (pintype "bidirectional"))
      (node (ref "UCA") (pin "P$29") (pinfunction "VSS2_P$29") (pintype "bidirectional"))
      (node (ref "UCA") (pin "P$39") (pinfunction "VSS3_P$39") (pintype "bidirectional"))
      (node (ref "UCA") (pin "P$6") (pinfunction "VSS1_P$6") (pintype "bidirectional"))
      (node (ref "UCA") (pin "PAD") (pinfunction "PAD_PAD") (pintype "bidirectional"))
      (node (ref "UCB") (pin "P$16") (pinfunction "AVSS_P$16") (pintype "bidirectional"))
      (node (ref "UCB") (pin "P$29") (pinfunction "VSS2_P$29") (pintype "bidirectional"))
      (node (ref "UCB") (pin "P$39") (pinfunction "VSS3_P$39") (pintype "bidirectional"))
      (node (ref "UCB") (pin "P$6") (pinfunction "VSS1_P$6") (pintype "bidirectional"))
      (node (ref "UCB") (pin "PAD") (pinfunction "PAD_PAD") (pintype "bidirectional"))
      (node (ref "UCC") (pin "13") (pinfunction "VSS_13") (pintype "bidirectional"))
      (node (ref "UFTDI") (pin "18") (pinfunction "GND2_18") (pintype "power_in"))
      (node (ref "UFTDI") (pin "21") (pinfunction "GND3_21") (pintype "power_in"))
      (node (ref "UFTDI") (pin "25") (pinfunction "AGND_25") (pintype "power_in"))
      (node (ref "UFTDI") (pin "26") (pinfunction "TEST_26") (pintype "input"))
      (node (ref "UFTDI") (pin "7") (pinfunction "GND1_7") (pintype "power_in"))
      (node (ref "X1") (pin "GND") (pinfunction "GND_GND") (pintype "bidirectional"))
    )
    (net (code "130") (name "Net-(CAN_DRV_A-RS)") (class "Default")
      (node (ref "CAN_DRV_A") (pin "8") (pinfunction "RS_8") (pintype "bidirectional"))
      (node (ref "RS_CAN_A") (pin "2") (pinfunction "2_2") (pintype "bidirectional"))
    )
    (net (code "131") (name "Net-(CAN_DRV_B-RS)") (class "Default")
      (node (ref "CAN_DRV_B") (pin "8") (pinfunction "RS_8") (pintype "bidirectional"))
      (node (ref "RS_CAN_B") (pin "2") (pinfunction "2_2") (pintype "bidirectional"))
    )
    (net (code "132") (name "Net-(DRV_DC1-CP1)") (class "Default")
      (node (ref "CP_DC1") (pin "1") (pinfunction "1_1") (pintype "bidirectional"))
      (node (ref "DRV_DC1") (pin "10") (pinfunction "CP1_10") (pintype "bidirectional"))
    )
    (net (code "133") (name "Net-(DRV_DC1-CP2)") (class "Default")
      (node (ref "CP_DC1") (pin "2") (pinfunction "2_2") (pintype "bidirectional"))
      (node (ref "DRV_DC1") (pin "11") (pinfunction "CP2_11") (pintype "bidirectional"))
    )
    (net (code "134") (name "Net-(DRV_DC1-MODE1)") (class "Default")
      (node (ref "DRV_DC1") (pin "16") (pinfunction "MODE1_16") (pintype "bidirectional"))
      (node (ref "R2_DC1") (pin "2") (pinfunction "2_2") (pintype "bidirectional"))
    )
    (net (code "135") (name "Net-(DRV_DC1-VCP)") (class "Default")
      (node (ref "CP2_DC1") (pin "2") (pinfunction "2_2") (pintype "bidirectional"))
      (node (ref "DRV_DC1") (pin "13") (pinfunction "VCP_13") (pintype "bidirectional"))
    )
    (net (code "136") (name "Net-(DRV_DC1-~{SLEEP})") (class "Default")
      (node (ref "DRV_DC1") (pin "3") (pinfunction "~{SLEEP}_3") (pintype "bidirectional"))
      (node (ref "R1_DC1") (pin "2") (pinfunction "2_2") (pintype "bidirectional"))
    )
    (net (code "137") (name "Net-(DRV_DC2-CP1)") (class "Default")
      (node (ref "CP_DC2") (pin "1") (pinfunction "1_1") (pintype "bidirectional"))
      (node (ref "DRV_DC2") (pin "10") (pinfunction "CP1_10") (pintype "bidirectional"))
    )
    (net (code "138") (name "Net-(DRV_DC2-CP2)") (class "Default")
      (node (ref "CP_DC2") (pin "2") (pinfunction "2_2") (pintype "bidirectional"))
      (node (ref "DRV_DC2") (pin "11") (pinfunction "CP2_11") (pintype "bidirectional"))
    )
    (net (code "139") (name "Net-(DRV_DC2-MODE1)") (class "Default")
      (node (ref "DRV_DC2") (pin "16") (pinfunction "MODE1_16") (pintype "bidirectional"))
      (node (ref "R2_DC2") (pin "2") (pinfunction "2_2") (pintype "bidirectional"))
    )
    (net (code "140") (name "Net-(DRV_DC2-VCP)") (class "Default")
      (node (ref "CP2_DC2") (pin "2") (pinfunction "2_2") (pintype "bidirectional"))
      (node (ref "DRV_DC2") (pin "13") (pinfunction "VCP_13") (pintype "bidirectional"))
    )
    (net (code "141") (name "Net-(DRV_DC2-~{SLEEP})") (class "Default")
      (node (ref "DRV_DC2") (pin "3") (pinfunction "~{SLEEP}_3") (pintype "bidirectional"))
      (node (ref "R1_DC2") (pin "2") (pinfunction "2_2") (pintype "bidirectional"))
    )
    (net (code "142") (name "Net-(DRV_DC3-CP1)") (class "Default")
      (node (ref "CP_DC3") (pin "1") (pinfunction "1_1") (pintype "bidirectional"))
      (node (ref "DRV_DC3") (pin "10") (pinfunction "CP1_10") (pintype "bidirectional"))
    )
    (net (code "143") (name "Net-(DRV_DC3-CP2)") (class "Default")
      (node (ref "CP_DC3") (pin "2") (pinfunction "2_2") (pintype "bidirectional"))
      (node (ref "DRV_DC3") (pin "11") (pinfunction "CP2_11") (pintype "bidirectional"))
    )
    (net (code "144") (name "Net-(DRV_DC3-MODE1)") (class "Default")
      (node (ref "DRV_DC3") (pin "16") (pinfunction "MODE1_16") (pintype "bidirectional"))
      (node (ref "R2_DC3") (pin "2") (pinfunction "2_2") (pintype "bidirectional"))
    )
    (net (code "145") (name "Net-(DRV_DC3-VCP)") (class "Default")
      (node (ref "CP2_DC3") (pin "2") (pinfunction "2_2") (pintype "bidirectional"))
      (node (ref "DRV_DC3") (pin "13") (pinfunction "VCP_13") (pintype "bidirectional"))
    )
    (net (code "146") (name "Net-(DRV_DC3-~{SLEEP})") (class "Default")
      (node (ref "DRV_DC3") (pin "3") (pinfunction "~{SLEEP}_3") (pintype "bidirectional"))
      (node (ref "R1_DC3") (pin "2") (pinfunction "2_2") (pintype "bidirectional"))
    )
    (net (code "147") (name "Net-(DRV_DC4-CP1)") (class "Default")
      (node (ref "CP_DC4") (pin "1") (pinfunction "1_1") (pintype "bidirectional"))
      (node (ref "DRV_DC4") (pin "10") (pinfunction "CP1_10") (pintype "bidirectional"))
    )
    (net (code "148") (name "Net-(DRV_DC4-CP2)") (class "Default")
      (node (ref "CP_DC4") (pin "2") (pinfunction "2_2") (pintype "bidirectional"))
      (node (ref "DRV_DC4") (pin "11") (pinfunction "CP2_11") (pintype "bidirectional"))
    )
    (net (code "149") (name "Net-(DRV_DC4-MODE1)") (class "Default")
      (node (ref "DRV_DC4") (pin "16") (pinfunction "MODE1_16") (pintype "bidirectional"))
      (node (ref "R2_DC4") (pin "2") (pinfunction "2_2") (pintype "bidirectional"))
    )
    (net (code "150") (name "Net-(DRV_DC4-VCP)") (class "Default")
      (node (ref "CP2_DC4") (pin "2") (pinfunction "2_2") (pintype "bidirectional"))
      (node (ref "DRV_DC4") (pin "13") (pinfunction "VCP_13") (pintype "bidirectional"))
    )
    (net (code "151") (name "Net-(DRV_DC4-~{SLEEP})") (class "Default")
      (node (ref "DRV_DC4") (pin "3") (pinfunction "~{SLEEP}_3") (pintype "bidirectional"))
      (node (ref "R1_DC4") (pin "2") (pinfunction "2_2") (pintype "bidirectional"))
    )
    (net (code "152") (name "Net-(DRV_DC5-CP1)") (class "Default")
      (node (ref "CP_DC5") (pin "1") (pinfunction "1_1") (pintype "bidirectional"))
      (node (ref "DRV_DC5") (pin "10") (pinfunction "CP1_10") (pintype "bidirectional"))
    )
    (net (code "153") (name "Net-(DRV_DC5-CP2)") (class "Default")
      (node (ref "CP_DC5") (pin "2") (pinfunction "2_2") (pintype "bidirectional"))
      (node (ref "DRV_DC5") (pin "11") (pinfunction "CP2_11") (pintype "bidirectional"))
    )
    (net (code "154") (name "Net-(DRV_DC5-MODE1)") (class "Default")
      (node (ref "DRV_DC5") (pin "16") (pinfunction "MODE1_16") (pintype "bidirectional"))
      (node (ref "R2_DC5") (pin "2") (pinfunction "2_2") (pintype "bidirectional"))
    )
    (net (code "155") (name "Net-(DRV_DC5-VCP)") (class "Default")
      (node (ref "CP2_DC5") (pin "2") (pinfunction "2_2") (pintype "bidirectional"))
      (node (ref "DRV_DC5") (pin "13") (pinfunction "VCP_13") (pintype "bidirectional"))
    )
    (net (code "156") (name "Net-(DRV_DC5-~{SLEEP})") (class "Default")
      (node (ref "DRV_DC5") (pin "3") (pinfunction "~{SLEEP}_3") (pintype "bidirectional"))
      (node (ref "R1_DC5") (pin "2") (pinfunction "2_2") (pintype "bidirectional"))
    )
    (net (code "157") (name "Net-(DRV_DC6-CP1)") (class "Default")
      (node (ref "CP_DC6") (pin "1") (pinfunction "1_1") (pintype "bidirectional"))
      (node (ref "DRV_DC6") (pin "10") (pinfunction "CP1_10") (pintype "bidirectional"))
    )
    (net (code "158") (name "Net-(DRV_DC6-CP2)") (class "Default")
      (node (ref "CP_DC6") (pin "2") (pinfunction "2_2") (pintype "bidirectional"))
      (node (ref "DRV_DC6") (pin "11") (pinfunction "CP2_11") (pintype "bidirectional"))
    )
    (net (code "159") (name "Net-(DRV_DC6-MODE1)") (class "Default")
      (node (ref "DRV_DC6") (pin "16") (pinfunction "MODE1_16") (pintype "bidirectional"))
      (node (ref "R2_DC6") (pin "2") (pinfunction "2_2") (pintype "bidirectional"))
    )
    (net (code "160") (name "Net-(DRV_DC6-VCP)") (class "Default")
      (node (ref "CP2_DC6") (pin "2") (pinfunction "2_2") (pintype "bidirectional"))
      (node (ref "DRV_DC6") (pin "13") (pinfunction "VCP_13") (pintype "bidirectional"))
    )
    (net (code "161") (name "Net-(DRV_DC6-~{SLEEP})") (class "Default")
      (node (ref "DRV_DC6") (pin "3") (pinfunction "~{SLEEP}_3") (pintype "bidirectional"))
      (node (ref "R1_DC6") (pin "2") (pinfunction "2_2") (pintype "bidirectional"))
    )
    (net (code "162") (name "Net-(DRV_DC7-CP1)") (class "Default")
      (node (ref "CP_DC7") (pin "1") (pinfunction "1_1") (pintype "bidirectional"))
      (node (ref "DRV_DC7") (pin "10") (pinfunction "CP1_10") (pintype "bidirectional"))
    )
    (net (code "163") (name "Net-(DRV_DC7-CP2)") (class "Default")
      (node (ref "CP_DC7") (pin "2") (pinfunction "2_2") (pintype "bidirectional"))
      (node (ref "DRV_DC7") (pin "11") (pinfunction "CP2_11") (pintype "bidirectional"))
    )
    (net (code "164") (name "Net-(DRV_DC7-MODE1)") (class "Default")
      (node (ref "DRV_DC7") (pin "16") (pinfunction "MODE1_16") (pintype "bidirectional"))
      (node (ref "R2_DC7") (pin "2") (pinfunction "2_2") (pintype "bidirectional"))
    )
    (net (code "165") (name "Net-(DRV_DC7-VCP)") (class "Default")
      (node (ref "CP2_DC7") (pin "2") (pinfunction "2_2") (pintype "bidirectional"))
      (node (ref "DRV_DC7") (pin "13") (pinfunction "VCP_13") (pintype "bidirectional"))
    )
    (net (code "166") (name "Net-(DRV_DC7-~{SLEEP})") (class "Default")
      (node (ref "DRV_DC7") (pin "3") (pinfunction "~{SLEEP}_3") (pintype "bidirectional"))
      (node (ref "R1_DC7") (pin "2") (pinfunction "2_2") (pintype "bidirectional"))
    )
    (net (code "167") (name "Net-(DRV_DC8-CP1)") (class "Default")
      (node (ref "CP_DC8") (pin "1") (pinfunction "1_1") (pintype "bidirectional"))
      (node (ref "DRV_DC8") (pin "10") (pinfunction "CP1_10") (pintype "bidirectional"))
    )
    (net (code "168") (name "Net-(DRV_DC8-CP2)") (class "Default")
      (node (ref "CP_DC8") (pin "2") (pinfunction "2_2") (pintype "bidirectional"))
      (node (ref "DRV_DC8") (pin "11") (pinfunction "CP2_11") (pintype "bidirectional"))
    )
    (net (code "169") (name "Net-(DRV_DC8-MODE1)") (class "Default")
      (node (ref "DRV_DC8") (pin "16") (pinfunction "MODE1_16") (pintype "bidirectional"))
      (node (ref "R2_DC8") (pin "2") (pinfunction "2_2") (pintype "bidirectional"))
    )
    (net (code "170") (name "Net-(DRV_DC8-VCP)") (class "Default")
      (node (ref "CP2_DC8") (pin "2") (pinfunction "2_2") (pintype "bidirectional"))
      (node (ref "DRV_DC8") (pin "13") (pinfunction "VCP_13") (pintype "bidirectional"))
    )
    (net (code "171") (name "Net-(DRV_DC8-~{SLEEP})") (class "Default")
      (node (ref "DRV_DC8") (pin "3") (pinfunction "~{SLEEP}_3") (pintype "bidirectional"))
      (node (ref "R1_DC8") (pin "2") (pinfunction "2_2") (pintype "bidirectional"))
    )
    (net (code "172") (name "Net-(LED_A-PadA)") (class "Default")
      (node (ref "LED_A") (pin "A") (pinfunction "A_A") (pintype "passive"))
      (node (ref "RLA") (pin "2") (pinfunction "2_2") (pintype "bidirectional"))
    )
    (net (code "173") (name "Net-(LED_B-PadA)") (class "Default")
      (node (ref "LED_B") (pin "A") (pinfunction "A_A") (pintype "passive"))
      (node (ref "RLB") (pin "2") (pinfunction "2_2") (pintype "bidirectional"))
    )
    (net (code "174") (name "Net-(LED_C-PadA)") (class "Default")
      (node (ref "LED_C") (pin "A") (pinfunction "A_A") (pintype "passive"))
      (node (ref "RLC") (pin "2") (pinfunction "2_2") (pintype "bidirectional"))
    )
    (net (code "175") (name "Net-(LED_RX-PadA)") (class "Default")
      (node (ref "LED_RX") (pin "A") (pinfunction "A_A") (pintype "passive"))
      (node (ref "RLRX") (pin "2") (pinfunction "2_2") (pintype "bidirectional"))
    )
    (net (code "176") (name "Net-(LED_TX-PadA)") (class "Default")
      (node (ref "LED_TX") (pin "A") (pinfunction "A_A") (pintype "passive"))
      (node (ref "RLTX") (pin "2") (pinfunction "2_2") (pintype "bidirectional"))
    )
    (net (code "177") (name "Net-(OPTO_1-Pad1)") (class "Default")
      (node (ref "OPTO_1") (pin "1") (pinfunction "1_1") (pintype "bidirectional"))
      (node (ref "ROL_4") (pin "2") (pinfunction "2_2") (pintype "bidirectional"))
    )
    (net (code "178") (name "Net-(OPTO_1-Pad3)") (class "Default")
      (node (ref "OPTO_1") (pin "3") (pinfunction "3_3") (pintype "bidirectional"))
      (node (ref "ROL_3") (pin "2") (pinfunction "2_2") (pintype "bidirectional"))
    )
    (net (code "179") (name "Net-(OPTO_1-Pad5)") (class "Default")
      (node (ref "OPTO_1") (pin "5") (pinfunction "5_5") (pintype "bidirectional"))
      (node (ref "ROL_2") (pin "2") (pinfunction "2_2") (pintype "bidirectional"))
    )
    (net (code "180") (name "Net-(OPTO_1-Pad7)") (class "Default")
      (node (ref "OPTO_1") (pin "7") (pinfunction "7_7") (pintype "bidirectional"))
      (node (ref "ROL_1") (pin "2") (pinfunction "2_2") (pintype "bidirectional"))
    )
    (net (code "181") (name "Net-(OPTO_2-Pad1)") (class "Default")
      (node (ref "OPTO_2") (pin "1") (pinfunction "1_1") (pintype "bidirectional"))
      (node (ref "ROL_5") (pin "2") (pinfunction "2_2") (pintype "bidirectional"))
    )
    (net (code "182") (name "Net-(OPTO_2-Pad3)") (class "Default")
      (node (ref "OPTO_2") (pin "3") (pinfunction "3_3") (pintype "bidirectional"))
      (node (ref "ROL_6") (pin "2") (pinfunction "2_2") (pintype "bidirectional"))
    )
    (net (code "183") (name "Net-(OPTO_2-Pad5)") (class "Default")
      (node (ref "OPTO_2") (pin "5") (pinfunction "5_5") (pintype "bidirectional"))
      (node (ref "ROL_7") (pin "2") (pinfunction "2_2") (pintype "bidirectional"))
    )
    (net (code "184") (name "Net-(OPTO_2-Pad7)") (class "Default")
      (node (ref "OPTO_2") (pin "7") (pinfunction "7_7") (pintype "bidirectional"))
      (node (ref "ROL_8") (pin "2") (pinfunction "2_2") (pintype "bidirectional"))
    )
    (net (code "185") (name "Net-(STEP_DRIVER_1-CP1)") (class "Default")
      (node (ref "CP_SM1") (pin "2") (pinfunction "2_2") (pintype "bidirectional"))
      (node (ref "STEP_DRIVER_1") (pin "P$1") (pinfunction "CP1_P$1") (pintype "bidirectional"))
    )
    (net (code "186") (name "Net-(STEP_DRIVER_1-CP2)") (class "Default")
      (node (ref "CP_SM1") (pin "1") (pinfunction "1_1") (pintype "bidirectional"))
      (node (ref "STEP_DRIVER_1") (pin "P$2") (pinfunction "CP2_P$2") (pintype "bidirectional"))
    )
    (net (code "187") (name "Net-(STEP_DRIVER_1-ISENA)") (class "Default")
      (node (ref "RISENA_SM1") (pin "1") (pinfunction "1_1") (pintype "bidirectional"))
      (node (ref "STEP_DRIVER_1") (pin "P$6") (pinfunction "ISENA_P$6") (pintype "bidirectional"))
    )
    (net (code "188") (name "Net-(STEP_DRIVER_1-ISENB)") (class "Default")
      (node (ref "RISENB_SM1") (pin "1") (pinfunction "1_1") (pintype "bidirectional"))
      (node (ref "STEP_DRIVER_1") (pin "P$9") (pinfunction "ISENB_P$9") (pintype "bidirectional"))
    )
    (net (code "189") (name "Net-(STEP_DRIVER_1-VCP)") (class "Default")
      (node (ref "CCP_SM1") (pin "2") (pinfunction "2_2") (pintype "bidirectional"))
      (node (ref "STEP_DRIVER_1") (pin "P$3") (pinfunction "VCP_P$3") (pintype "bidirectional"))
    )
    (net (code "190") (name "VP1") (class "Default")
      (node (ref "FDP_BOT") (pin "P$7") (pinfunction "P$7_P$7") (pintype "bidirectional"))
      (node (ref "FDP_BOT") (pin "P$9") (pinfunction "P$9_P$9") (pintype "bidirectional"))
      (node (ref "ROP_1") (pin "2") (pinfunction "2_2") (pintype "bidirectional"))
      (node (ref "ROP_2") (pin "2") (pinfunction "2_2") (pintype "bidirectional"))
      (node (ref "ROP_3") (pin "2") (pinfunction "2_2") (pintype "bidirectional"))
      (node (ref "ROP_4") (pin "2") (pinfunction "2_2") (pintype "bidirectional"))
      (node (ref "ROP_5") (pin "2") (pinfunction "2_2") (pintype "bidirectional"))
      (node (ref "ROP_6") (pin "2") (pinfunction "2_2") (pintype "bidirectional"))
      (node (ref "ROP_7") (pin "2") (pinfunction "2_2") (pintype "bidirectional"))
      (node (ref "ROP_8") (pin "2") (pinfunction "2_2") (pintype "bidirectional"))
      (node (ref "SERVO1") (pin "2") (pinfunction "2_2") (pintype "passive"))
      (node (ref "SERVO2") (pin "2") (pinfunction "2_2") (pintype "passive"))
      (node (ref "SERVO3") (pin "2") (pinfunction "2_2") (pintype "passive"))
      (node (ref "SERVO4") (pin "2") (pinfunction "2_2") (pintype "passive"))
      (node (ref "SERVO5") (pin "2") (pinfunction "2_2") (pintype "passive"))
      (node (ref "SERVO6") (pin "2") (pinfunction "2_2") (pintype "passive"))
      (node (ref "SERVO7") (pin "2") (pinfunction "2_2") (pintype "passive"))
      (node (ref "SERVO8") (pin "2") (pinfunction "2_2") (pintype "passive"))
    )
    (net (code "191") (name "VP2") (class "Default")
      (node (ref "FDP_BOT") (pin "P$11") (pinfunction "P$11_P$11") (pintype "bidirectional"))
      (node (ref "FDP_BOT") (pin "P$13") (pinfunction "P$13_P$13") (pintype "bidirectional"))
      (node (ref "SERVO_DIG_1") (pin "2") (pinfunction "2_2") (pintype "passive"))
      (node (ref "SERVO_DIG_2") (pin "2") (pinfunction "2_2") (pintype "passive"))
    )
    (net (code "192") (name "VP3") (class "Default")
      (node (ref "CP2_DC1") (pin "1") (pinfunction "1_1") (pintype "bidirectional"))
      (node (ref "CP2_DC2") (pin "1") (pinfunction "1_1") (pintype "bidirectional"))
      (node (ref "CP2_DC3") (pin "1") (pinfunction "1_1") (pintype "bidirectional"))
      (node (ref "CP2_DC4") (pin "1") (pinfunction "1_1") (pintype "bidirectional"))
      (node (ref "CP2_DC5") (pin "1") (pinfunction "1_1") (pintype "bidirectional"))
      (node (ref "CP2_DC6") (pin "1") (pinfunction "1_1") (pintype "bidirectional"))
      (node (ref "CP2_DC7") (pin "1") (pinfunction "1_1") (pintype "bidirectional"))
      (node (ref "CP2_DC8") (pin "1") (pinfunction "1_1") (pintype "bidirectional"))
      (node (ref "CS1_DC1") (pin "+") (pinfunction "+_+") (pintype "passive"))
      (node (ref "CS1_DC2") (pin "+") (pinfunction "+_+") (pintype "passive"))
      (node (ref "CS1_DC3") (pin "+") (pinfunction "+_+") (pintype "passive"))
      (node (ref "CS1_DC4") (pin "+") (pinfunction "+_+") (pintype "passive"))
      (node (ref "CS1_DC5") (pin "+") (pinfunction "+_+") (pintype "passive"))
      (node (ref "CS1_DC6") (pin "+") (pinfunction "+_+") (pintype "passive"))
      (node (ref "CS1_DC7") (pin "+") (pinfunction "+_+") (pintype "passive"))
      (node (ref "CS1_DC8") (pin "+") (pinfunction "+_+") (pintype "passive"))
      (node (ref "CS2_DC1") (pin "2") (pinfunction "2_2") (pintype "bidirectional"))
      (node (ref "CS2_DC2") (pin "2") (pinfunction "2_2") (pintype "bidirectional"))
      (node (ref "CS2_DC3") (pin "2") (pinfunction "2_2") (pintype "bidirectional"))
      (node (ref "CS2_DC4") (pin "2") (pinfunction "2_2") (pintype "bidirectional"))
      (node (ref "CS2_DC5") (pin "2") (pinfunction "2_2") (pintype "bidirectional"))
      (node (ref "CS2_DC6") (pin "2") (pinfunction "2_2") (pintype "bidirectional"))
      (node (ref "CS2_DC7") (pin "2") (pinfunction "2_2") (pintype "bidirectional"))
      (node (ref "CS2_DC8") (pin "2") (pinfunction "2_2") (pintype "bidirectional"))
      (node (ref "DRV_DC1") (pin "8") (pinfunction "VBB_8") (pintype "bidirectional"))
      (node (ref "DRV_DC2") (pin "8") (pinfunction "VBB_8") (pintype "bidirectional"))
      (node (ref "DRV_DC3") (pin "8") (pinfunction "VBB_8") (pintype "bidirectional"))
      (node (ref "DRV_DC4") (pin "8") (pinfunction "VBB_8") (pintype "bidirectional"))
      (node (ref "DRV_DC5") (pin "8") (pinfunction "VBB_8") (pintype "bidirectional"))
      (node (ref "DRV_DC6") (pin "8") (pinfunction "VBB_8") (pintype "bidirectional"))
      (node (ref "DRV_DC7") (pin "8") (pinfunction "VBB_8") (pintype "bidirectional"))
      (node (ref "DRV_DC8") (pin "8") (pinfunction "VBB_8") (pintype "bidirectional"))
      (node (ref "FDP_TOP") (pin "P$15") (pinfunction "P$15_P$15") (pintype "bidirectional"))
      (node (ref "FDP_TOP") (pin "P$17") (pinfunction "P$17_P$17") (pintype "bidirectional"))
    )
    (net (code "193") (name "VP5") (class "Default")
      (node (ref "CCP_SM1") (pin "1") (pinfunction "1_1") (pintype "bidirectional"))
      (node (ref "FDP_BOT") (pin "P$23") (pinfunction "P$23_P$23") (pintype "bidirectional"))
      (node (ref "FDP_BOT") (pin "P$25") (pinfunction "P$25_P$25") (pintype "bidirectional"))
      (node (ref "STEP_DRIVER_1") (pin "P$11") (pinfunction "VMB_P$11") (pintype "bidirectional"))
      (node (ref "STEP_DRIVER_1") (pin "P$4") (pinfunction "VMA_P$4") (pintype "bidirectional"))
    )
    (net (code "194") (name "unconnected-(CAN_DRV_A-VREF-Pad5)") (class "Default")
      (node (ref "CAN_DRV_A") (pin "5") (pinfunction "VREF_5") (pintype "bidirectional"))
    )
    (net (code "195") (name "unconnected-(CAN_DRV_B-VREF-Pad5)") (class "Default")
      (node (ref "CAN_DRV_B") (pin "5") (pinfunction "VREF_5") (pintype "bidirectional"))
    )
    (net (code "196") (name "unconnected-(DRV_DC1-VPROPI-Pad14)") (class "Default")
      (node (ref "DRV_DC1") (pin "14") (pinfunction "VPROPI_14") (pintype "bidirectional"))
    )
    (net (code "197") (name "unconnected-(DRV_DC1-~{FAULT}-Pad15)") (class "Default")
      (node (ref "DRV_DC1") (pin "15") (pinfunction "~{FAULT}_15") (pintype "bidirectional"))
    )
    (net (code "198") (name "unconnected-(DRV_DC2-VPROPI-Pad14)") (class "Default")
      (node (ref "DRV_DC2") (pin "14") (pinfunction "VPROPI_14") (pintype "bidirectional"))
    )
    (net (code "199") (name "unconnected-(DRV_DC2-~{FAULT}-Pad15)") (class "Default")
      (node (ref "DRV_DC2") (pin "15") (pinfunction "~{FAULT}_15") (pintype "bidirectional"))
    )
    (net (code "200") (name "unconnected-(DRV_DC3-VPROPI-Pad14)") (class "Default")
      (node (ref "DRV_DC3") (pin "14") (pinfunction "VPROPI_14") (pintype "bidirectional"))
    )
    (net (code "201") (name "unconnected-(DRV_DC3-~{FAULT}-Pad15)") (class "Default")
      (node (ref "DRV_DC3") (pin "15") (pinfunction "~{FAULT}_15") (pintype "bidirectional"))
    )
    (net (code "202") (name "unconnected-(DRV_DC4-VPROPI-Pad14)") (class "Default")
      (node (ref "DRV_DC4") (pin "14") (pinfunction "VPROPI_14") (pintype "bidirectional"))
    )
    (net (code "203") (name "unconnected-(DRV_DC4-~{FAULT}-Pad15)") (class "Default")
      (node (ref "DRV_DC4") (pin "15") (pinfunction "~{FAULT}_15") (pintype "bidirectional"))
    )
    (net (code "204") (name "unconnected-(DRV_DC5-VPROPI-Pad14)") (class "Default")
      (node (ref "DRV_DC5") (pin "14") (pinfunction "VPROPI_14") (pintype "bidirectional"))
    )
    (net (code "205") (name "unconnected-(DRV_DC5-~{FAULT}-Pad15)") (class "Default")
      (node (ref "DRV_DC5") (pin "15") (pinfunction "~{FAULT}_15") (pintype "bidirectional"))
    )
    (net (code "206") (name "unconnected-(DRV_DC6-VPROPI-Pad14)") (class "Default")
      (node (ref "DRV_DC6") (pin "14") (pinfunction "VPROPI_14") (pintype "bidirectional"))
    )
    (net (code "207") (name "unconnected-(DRV_DC6-~{FAULT}-Pad15)") (class "Default")
      (node (ref "DRV_DC6") (pin "15") (pinfunction "~{FAULT}_15") (pintype "bidirectional"))
    )
    (net (code "208") (name "unconnected-(DRV_DC7-VPROPI-Pad14)") (class "Default")
      (node (ref "DRV_DC7") (pin "14") (pinfunction "VPROPI_14") (pintype "bidirectional"))
    )
    (net (code "209") (name "unconnected-(DRV_DC7-~{FAULT}-Pad15)") (class "Default")
      (node (ref "DRV_DC7") (pin "15") (pinfunction "~{FAULT}_15") (pintype "bidirectional"))
    )
    (net (code "210") (name "unconnected-(DRV_DC8-VPROPI-Pad14)") (class "Default")
      (node (ref "DRV_DC8") (pin "14") (pinfunction "VPROPI_14") (pintype "bidirectional"))
    )
    (net (code "211") (name "unconnected-(DRV_DC8-~{FAULT}-Pad15)") (class "Default")
      (node (ref "DRV_DC8") (pin "15") (pinfunction "~{FAULT}_15") (pintype "bidirectional"))
    )
    (net (code "212") (name "unconnected-(FDP_BOT-PadP$1)") (class "Default")
      (node (ref "FDP_BOT") (pin "P$1") (pinfunction "P$1_P$1") (pintype "bidirectional"))
    )
    (net (code "213") (name "unconnected-(FDP_BOT-PadP$6)") (class "Default")
      (node (ref "FDP_BOT") (pin "P$6") (pinfunction "P$6_P$6") (pintype "bidirectional"))
    )
    (net (code "214") (name "unconnected-(FDP_BOT-PadP$15)") (class "Default")
      (node (ref "FDP_BOT") (pin "P$15") (pinfunction "P$15_P$15") (pintype "bidirectional"))
    )
    (net (code "215") (name "unconnected-(FDP_BOT-PadP$17)") (class "Default")
      (node (ref "FDP_BOT") (pin "P$17") (pinfunction "P$17_P$17") (pintype "bidirectional"))
    )
    (net (code "216") (name "unconnected-(FDP_BOT-PadP$19)") (class "Default")
      (node (ref "FDP_BOT") (pin "P$19") (pinfunction "P$19_P$19") (pintype "bidirectional"))
    )
    (net (code "217") (name "unconnected-(FDP_BOT-PadP$21)") (class "Default")
      (node (ref "FDP_BOT") (pin "P$21") (pinfunction "P$21_P$21") (pintype "bidirectional"))
    )
    (net (code "218") (name "unconnected-(FDP_TOP-PadP$5)") (class "Default")
      (node (ref "FDP_TOP") (pin "P$5") (pinfunction "P$5_P$5") (pintype "bidirectional"))
    )
    (net (code "219") (name "unconnected-(FDP_TOP-PadP$7)") (class "Default")
      (node (ref "FDP_TOP") (pin "P$7") (pinfunction "P$7_P$7") (pintype "bidirectional"))
    )
    (net (code "220") (name "unconnected-(FDP_TOP-PadP$9)") (class "Default")
      (node (ref "FDP_TOP") (pin "P$9") (pinfunction "P$9_P$9") (pintype "bidirectional"))
    )
    (net (code "221") (name "unconnected-(FDP_TOP-PadP$11)") (class "Default")
      (node (ref "FDP_TOP") (pin "P$11") (pinfunction "P$11_P$11") (pintype "bidirectional"))
    )
    (net (code "222") (name "unconnected-(FDP_TOP-PadP$13)") (class "Default")
      (node (ref "FDP_TOP") (pin "P$13") (pinfunction "P$13_P$13") (pintype "bidirectional"))
    )
    (net (code "223") (name "unconnected-(FDP_TOP-PadP$19)") (class "Default")
      (node (ref "FDP_TOP") (pin "P$19") (pinfunction "P$19_P$19") (pintype "bidirectional"))
    )
    (net (code "224") (name "unconnected-(FDP_TOP-PadP$21)") (class "Default")
      (node (ref "FDP_TOP") (pin "P$21") (pinfunction "P$21_P$21") (pintype "bidirectional"))
    )
    (net (code "225") (name "unconnected-(FDP_TOP-PadP$23)") (class "Default")
      (node (ref "FDP_TOP") (pin "P$23") (pinfunction "P$23_P$23") (pintype "bidirectional"))
    )
    (net (code "226") (name "unconnected-(FDP_TOP-PadP$25)") (class "Default")
      (node (ref "FDP_TOP") (pin "P$25") (pinfunction "P$25_P$25") (pintype "bidirectional"))
    )
    (net (code "227") (name "unconnected-(STEP_DRIVER_1-~{FAULT}-PadP$18)") (class "Default")
      (node (ref "STEP_DRIVER_1") (pin "P$18") (pinfunction "~{FAULT}_P$18") (pintype "bidirectional"))
    )
    (net (code "228") (name "unconnected-(UCC-NC1-Pad14)") (class "Default")
      (node (ref "UCC") (pin "14") (pinfunction "NC1_14") (pintype "no_connect"))
    )
    (net (code "229") (name "unconnected-(UCC-NC2-Pad15)") (class "Default")
      (node (ref "UCC") (pin "15") (pinfunction "NC2_15") (pintype "no_connect"))
    )
    (net (code "230") (name "unconnected-(UFTDI-3V3OUT-Pad17)") (class "Default")
      (node (ref "UFTDI") (pin "17") (pinfunction "3V3OUT_17") (pintype "output"))
    )
    (net (code "231") (name "unconnected-(UFTDI-CTS-Pad11)") (class "Default")
      (node (ref "UFTDI") (pin "11") (pinfunction "CTS_11") (pintype "bidirectional"))
    )
    (net (code "232") (name "unconnected-(UFTDI-DTR-Pad2)") (class "Default")
      (node (ref "UFTDI") (pin "2") (pinfunction "DTR_2") (pintype "bidirectional"))
    )
    (net (code "233") (name "unconnected-(UFTDI-RTS-Pad3)") (class "Default")
      (node (ref "UFTDI") (pin "3") (pinfunction "RTS_3") (pintype "bidirectional"))
    )
    (net (code "234") (name "unconnected-(X1-PadVBUS)") (class "Default")
      (node (ref "X1") (pin "VBUS") (pinfunction "VBUS_VBUS") (pintype "bidirectional"))
    )
  )
)
